# evalboard-005.net
KiCad netlist of a schematic drawn in EAGLE
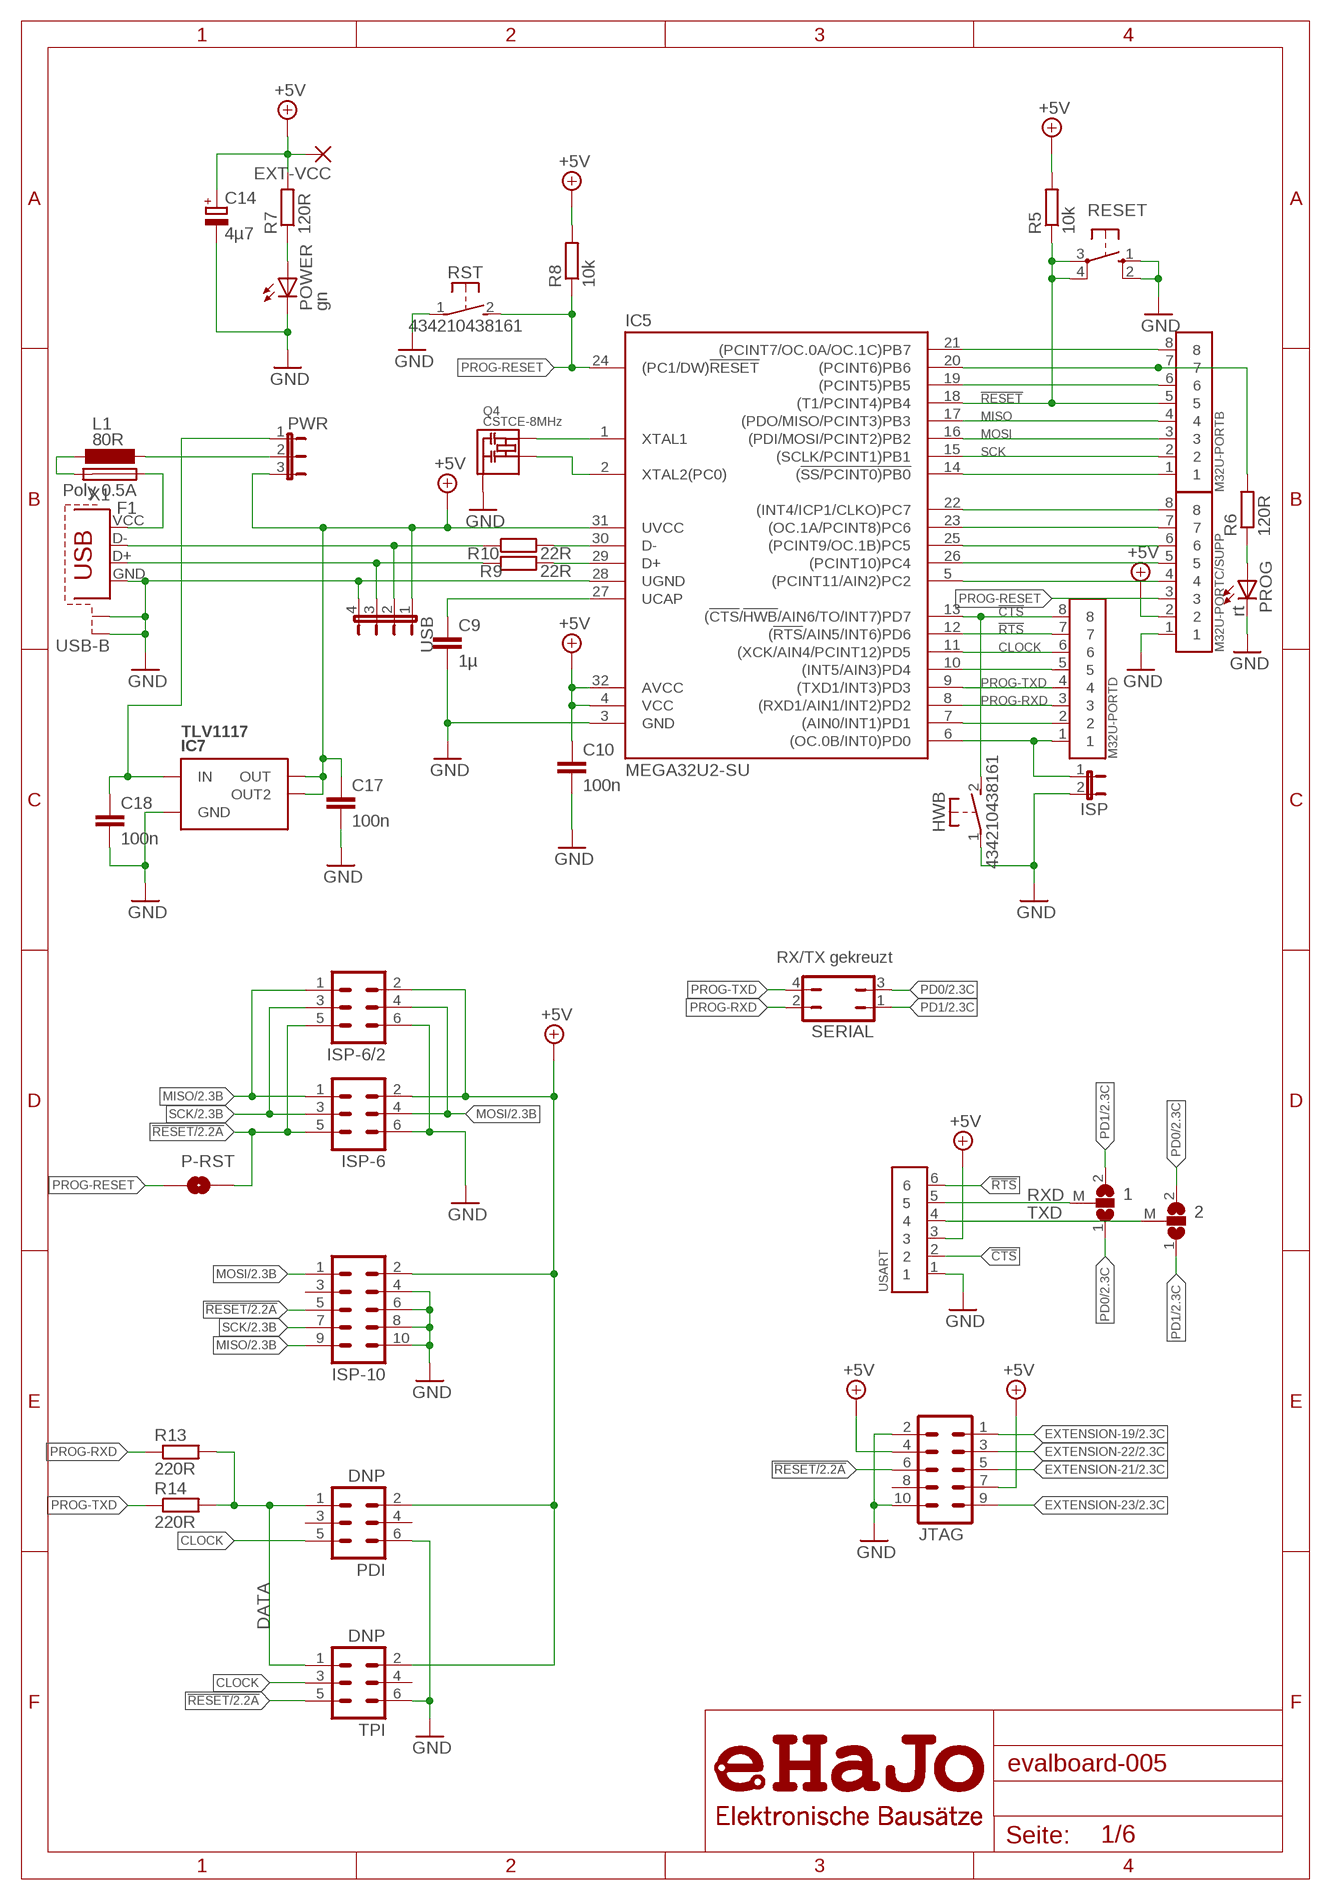
[diagram p0: schematic, sheet 1]
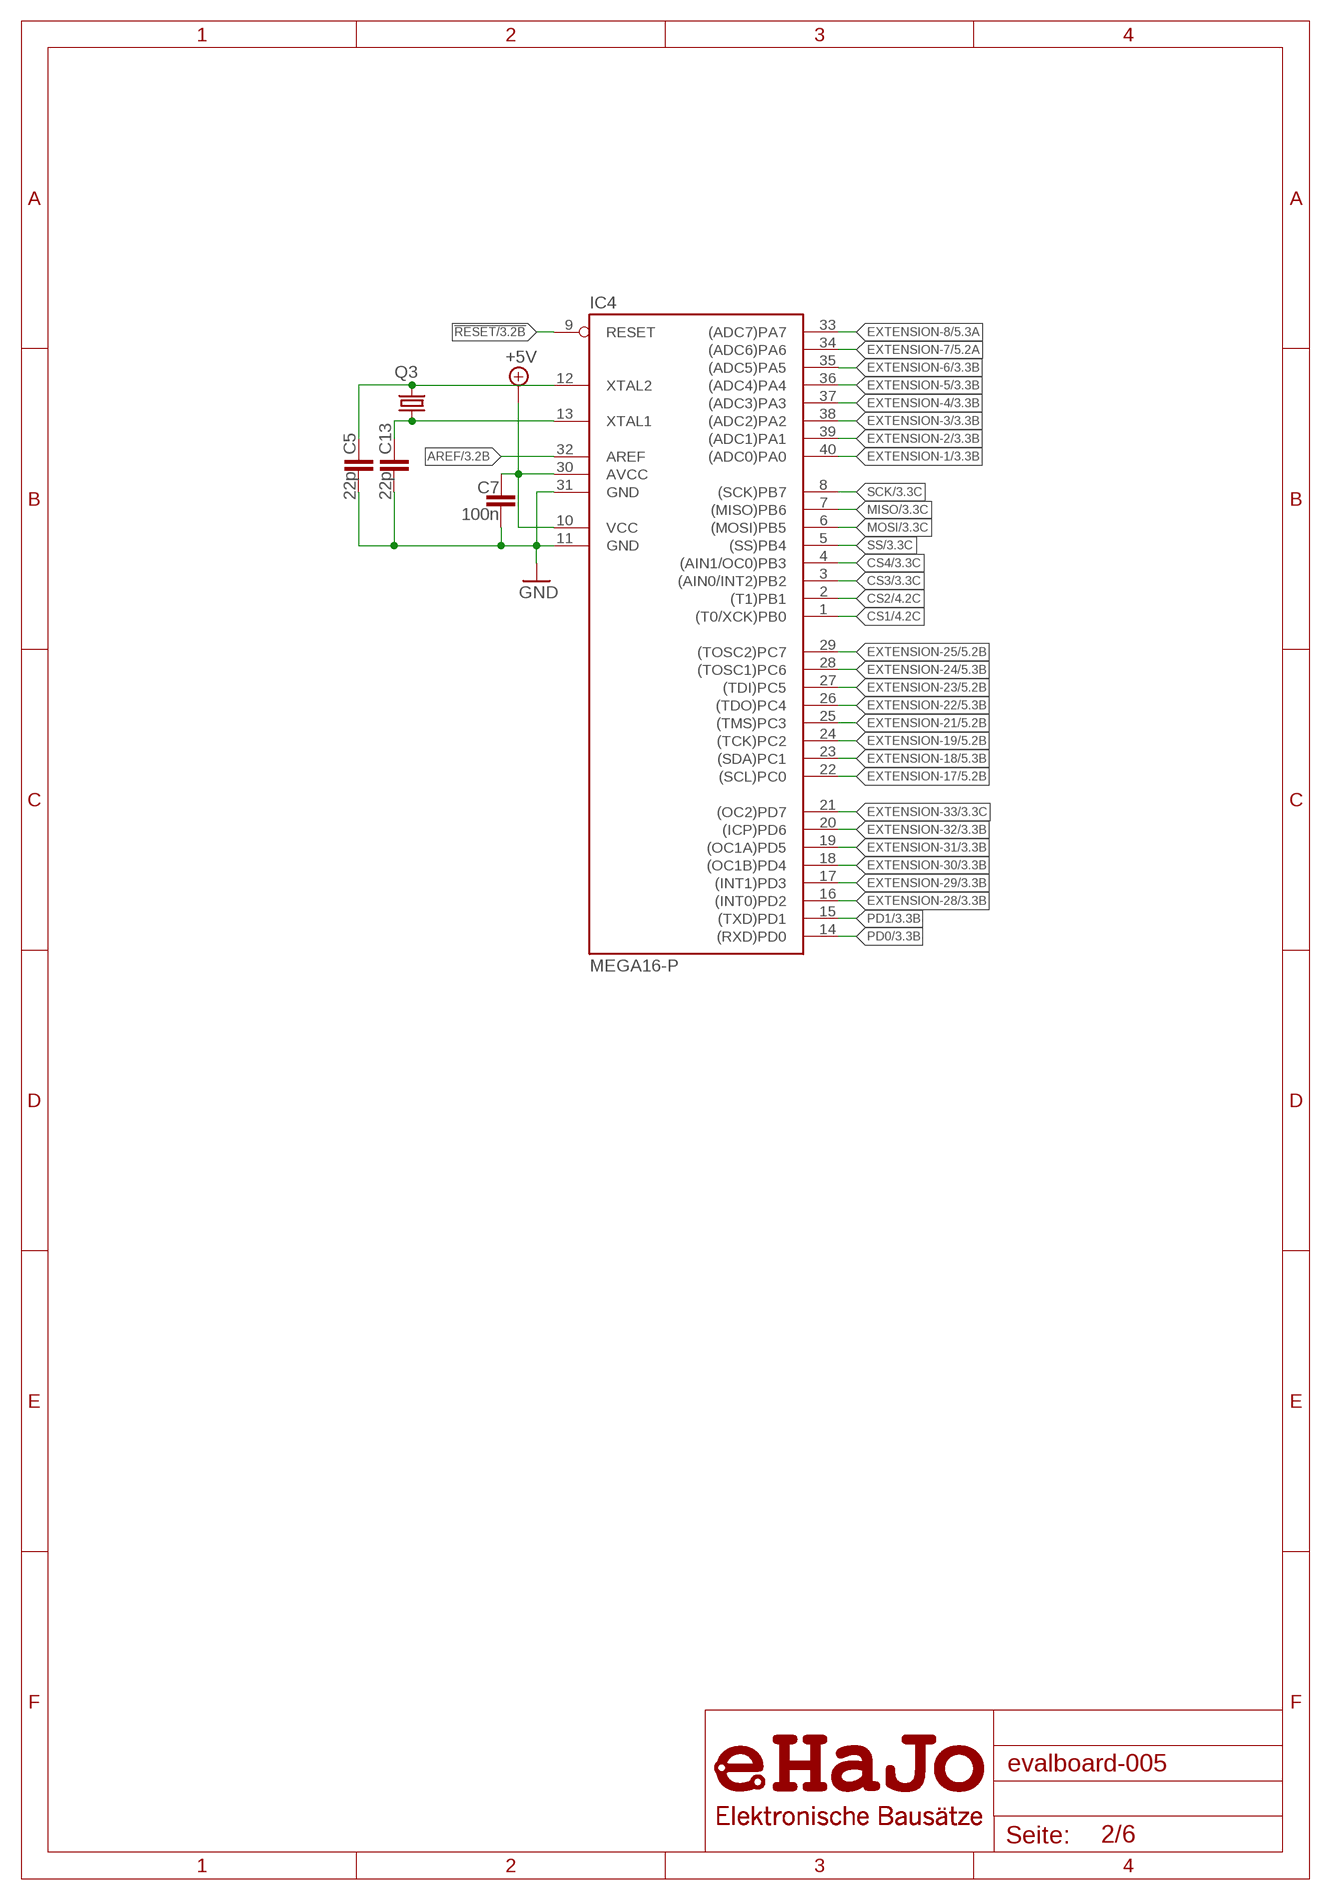
[diagram p1: schematic, sheet 2]
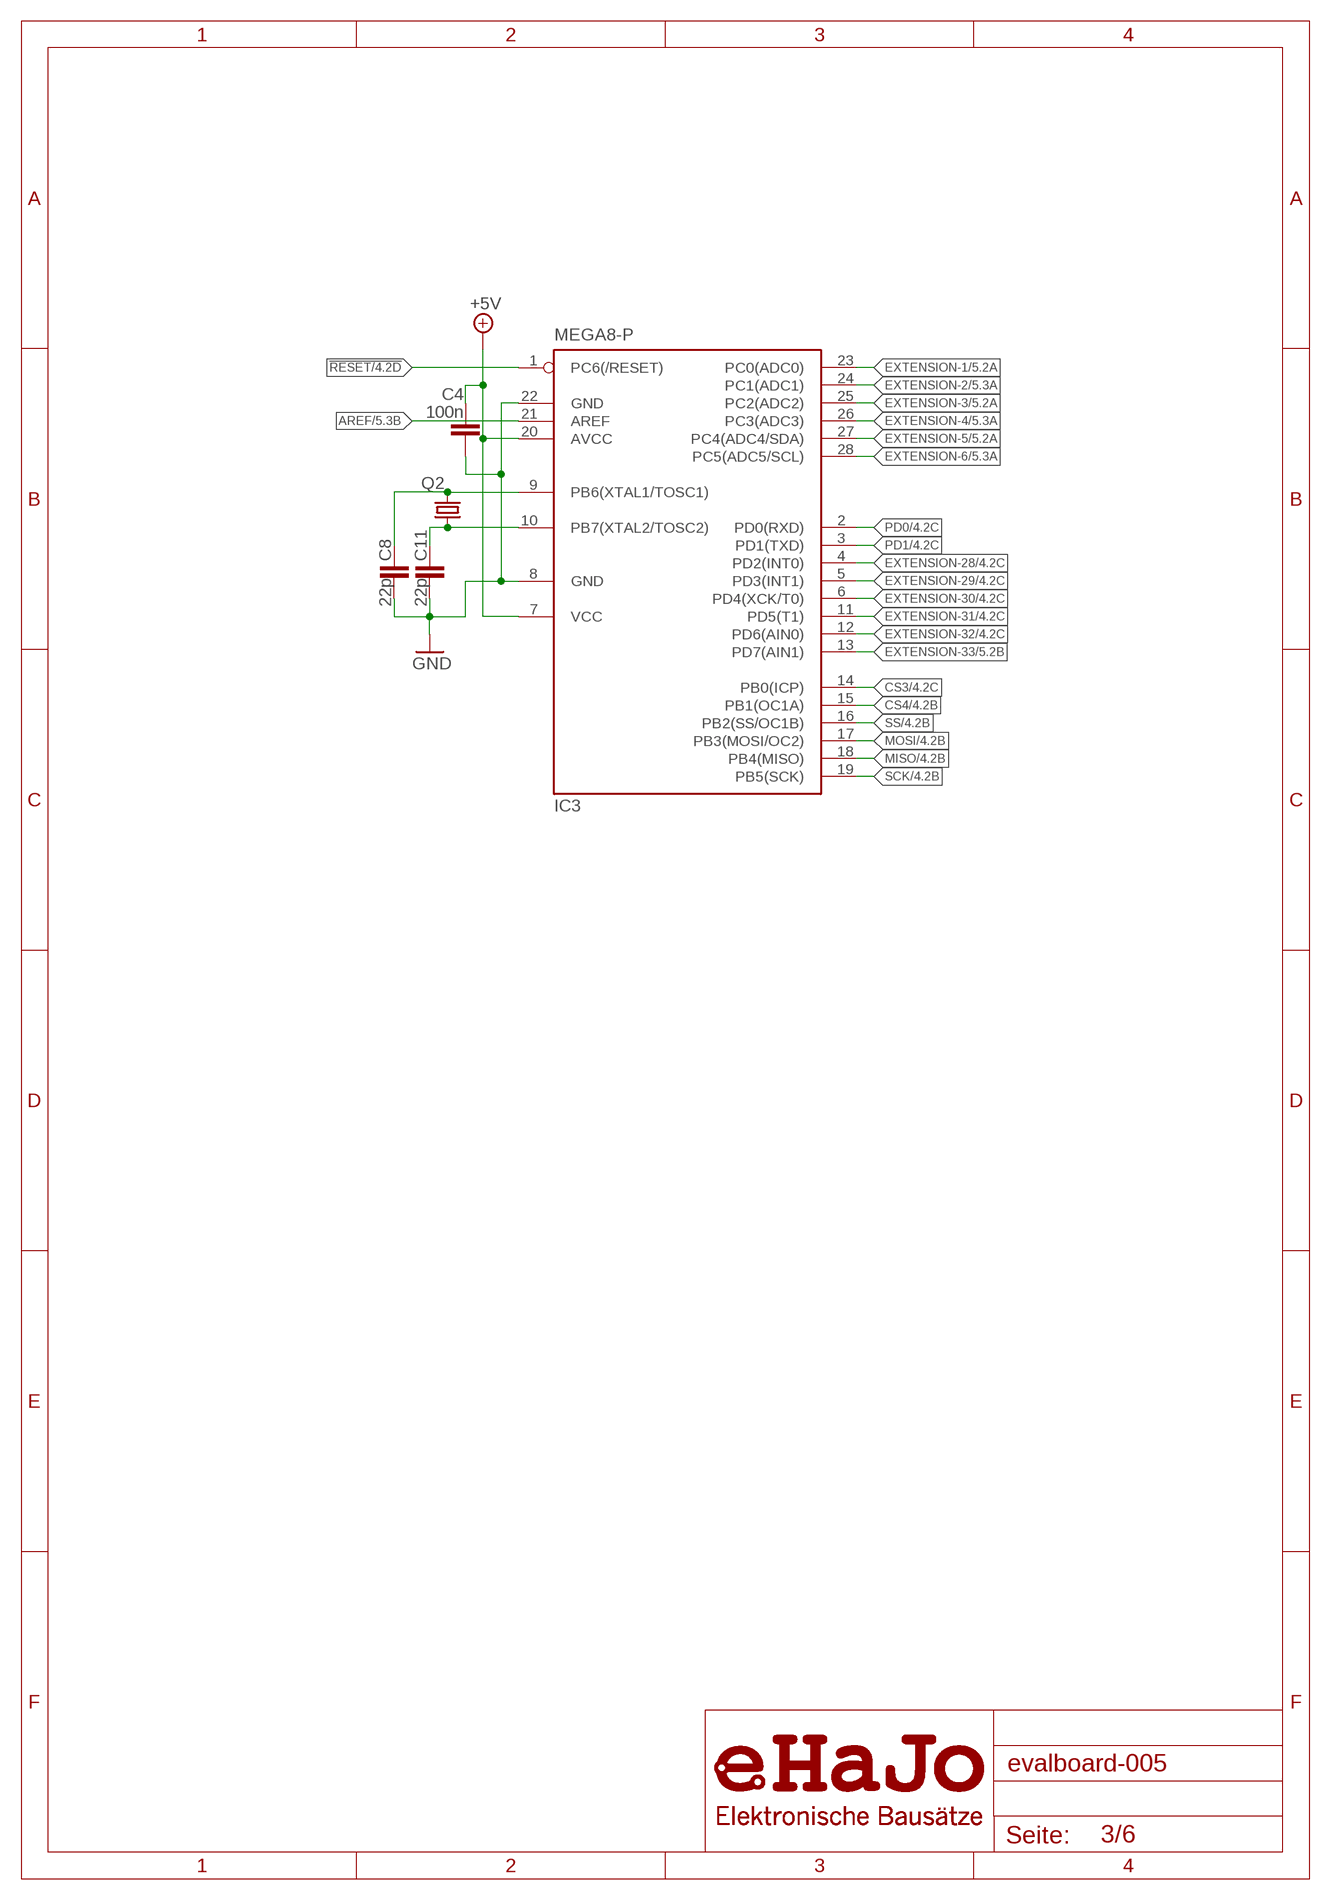
[diagram p2: schematic, sheet 3]
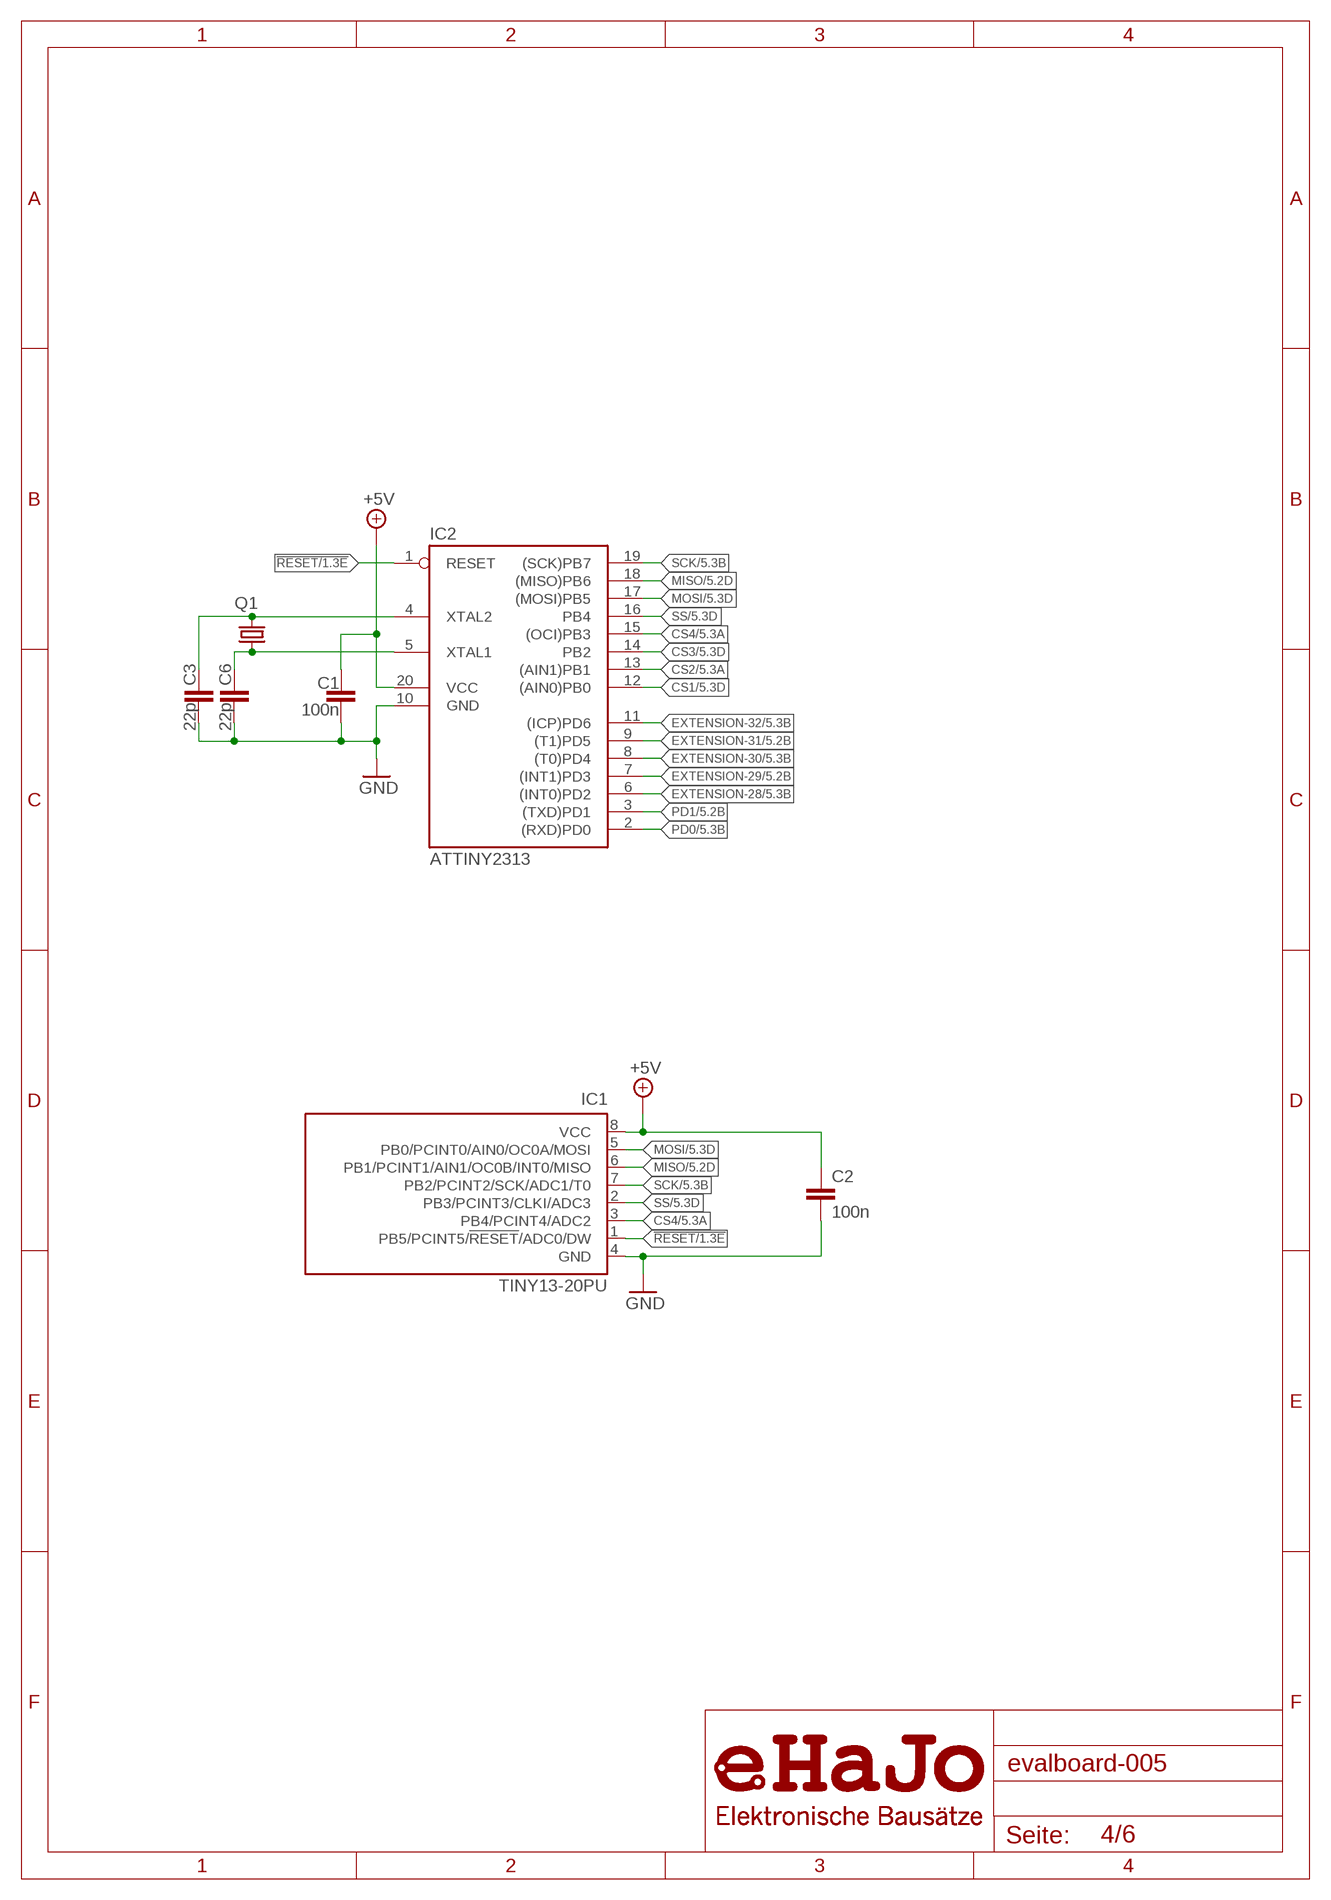
[diagram p3: schematic, sheet 4]
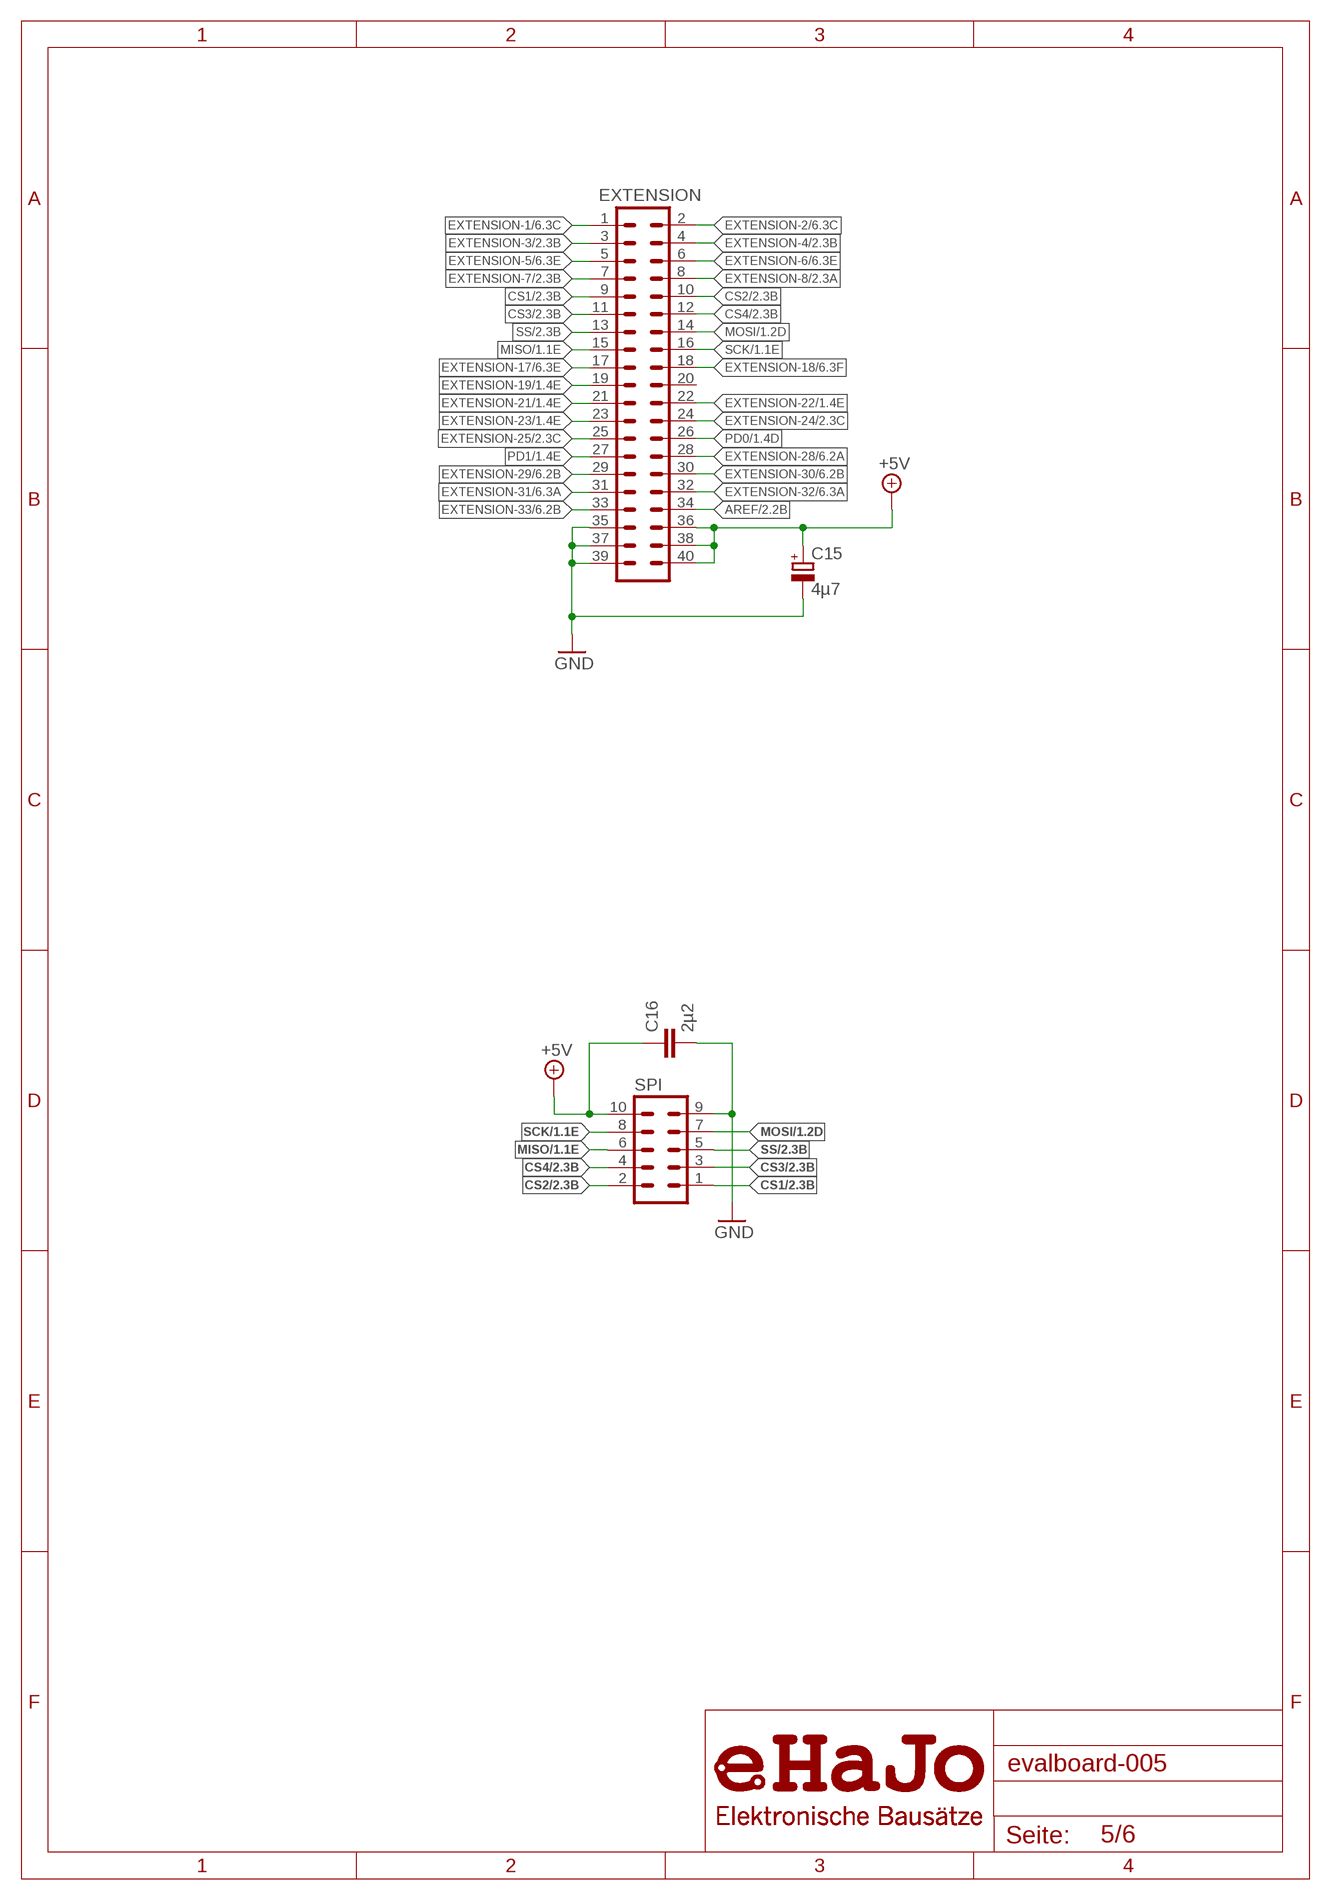
[diagram p4: schematic, sheet 5]
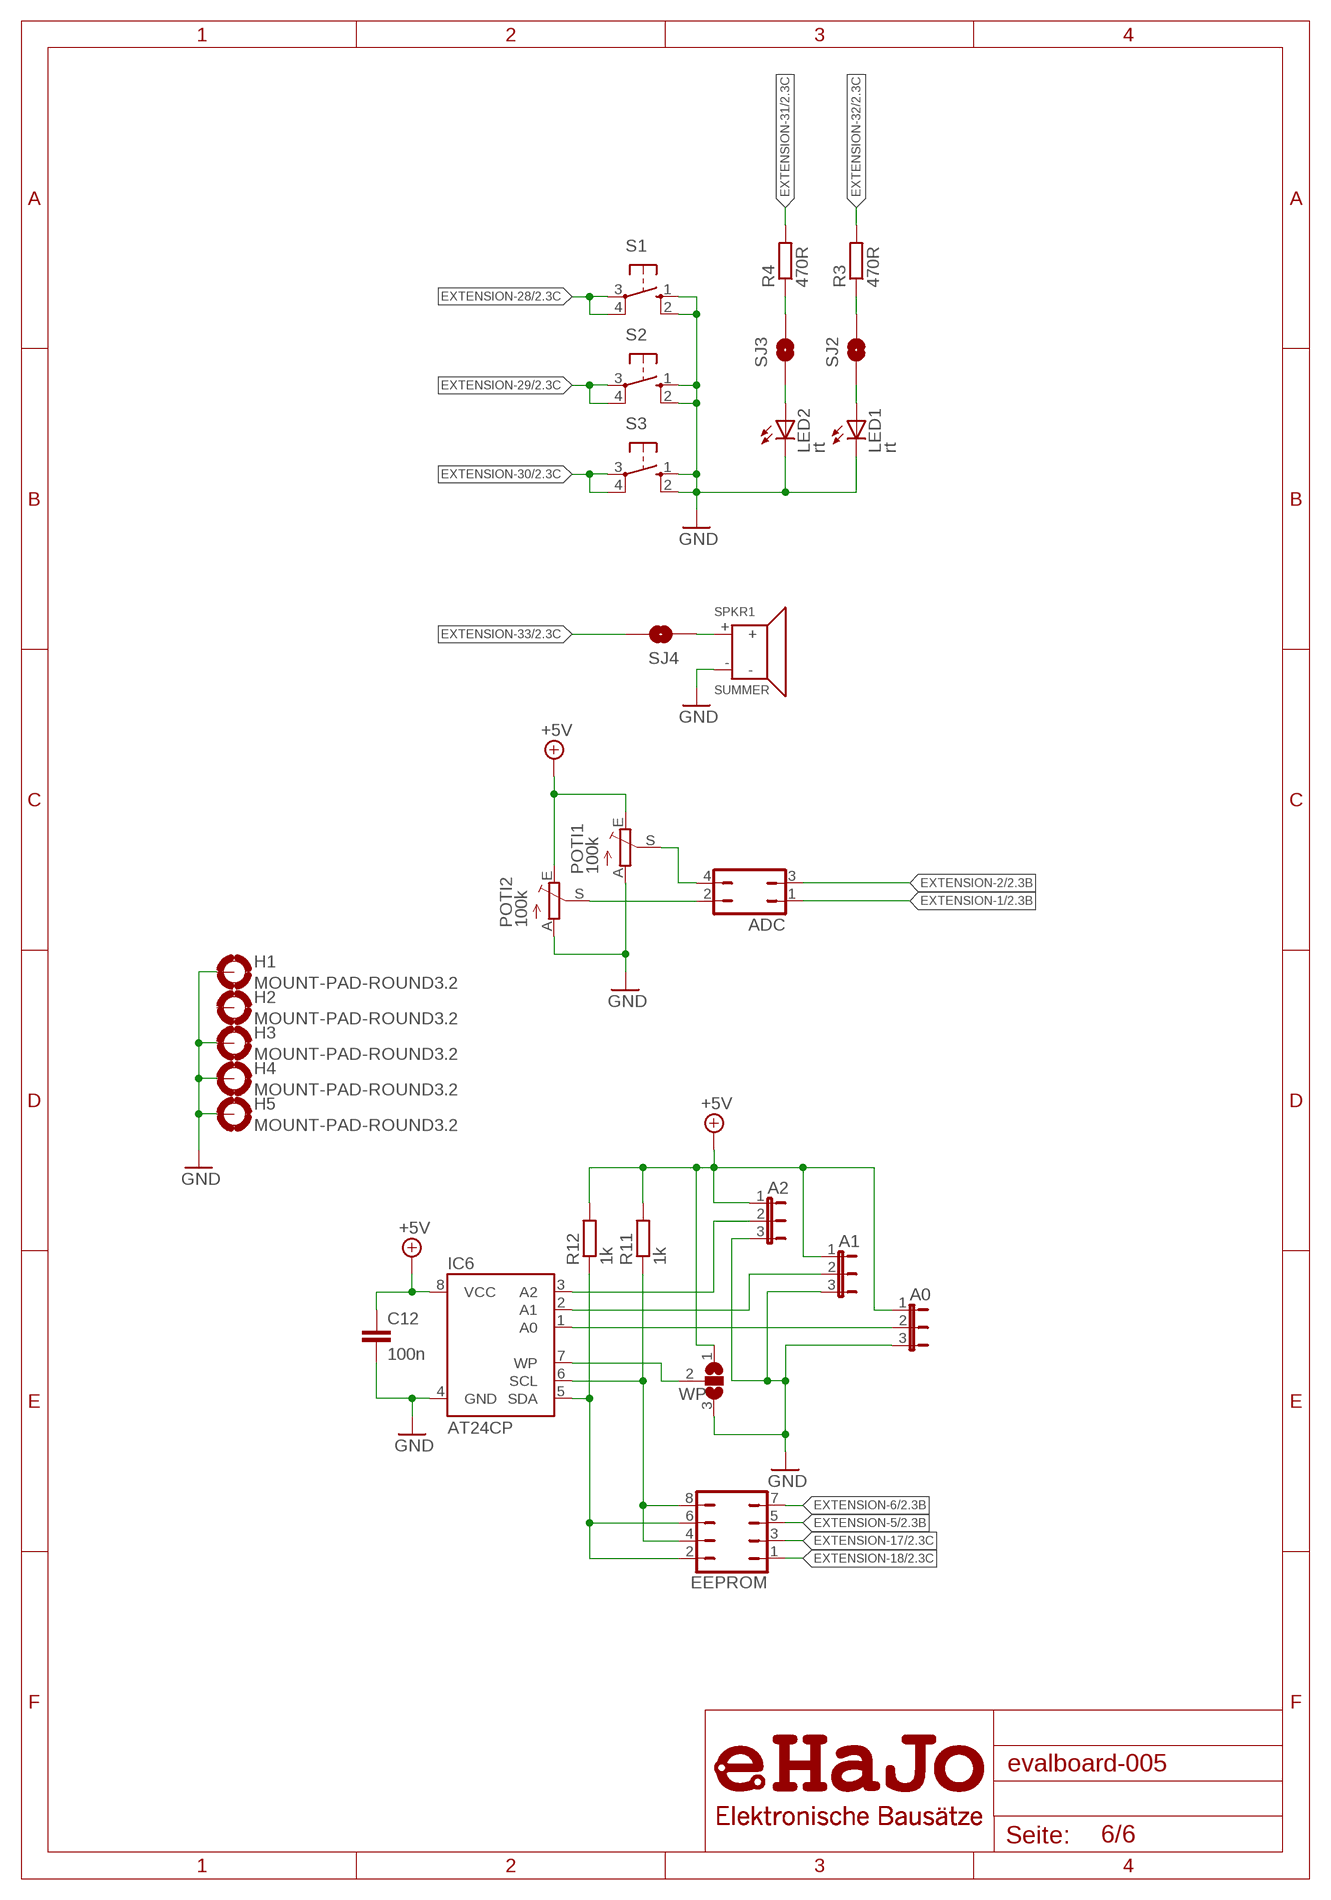
[diagram p5: schematic, sheet 6]

(export (version "E")
  (design (tool "Eeschema 10.0.6"))
  (components
    (comp (ref "1")
      (value "SJ2WS")
      (footprint "eagle-import:SJ2-S")
      (libsource (lib "eagle-import") (part "SJ2WS"))
    )
    (comp (ref "2")
      (value "SJ2WS")
      (footprint "eagle-import:SJ2-S")
      (libsource (lib "eagle-import") (part "SJ2WS"))
    )
    (comp (ref "C9")
      (value "1µ")
      (footprint "eagle-import:C0805")
      (libsource (lib "eagle-import") (part "CC0805"))
    )
    (comp (ref "C10")
      (value "100n")
      (footprint "eagle-import:C0805")
      (libsource (lib "eagle-import") (part "CC0805"))
    )
    (comp (ref "C14")
      (value "4µ7")
      (footprint "eagle-import:E2,5-6E")
      (libsource (lib "eagle-import") (part "CPOLE2,5-6E"))
    )
    (comp (ref "C17")
      (value "100n")
      (footprint "eagle-import:C0805")
      (libsource (lib "eagle-import") (part "CC0805"))
    )
    (comp (ref "C18")
      (value "100n")
      (footprint "eagle-import:C0805")
      (libsource (lib "eagle-import") (part "CC0805"))
    )
    (comp (ref "EXT-VCC")
      (value "2,54/1,0")
      (footprint "eagle-import:2,54_1,0")
      (libsource (lib "eagle-import") (part "2,54/1,0"))
    )
    (comp (ref "F1")
      (value "Poly 0.5A")
      (footprint "eagle-import:1206")
      (libsource (lib "eagle-import") (part "FUSE1206"))
    )
    (comp (ref "HWB")
      (value "434210438161")
      (footprint "eagle-import:WS-TRS-6,0X3,5")
      (libsource (lib "eagle-import") (part "434121043816"))
    )
    (comp (ref "IC5")
      (value "MEGA32U2-SU")
      (footprint "eagle-import:TQFP32-08")
      (libsource (lib "eagle-import") (part "MEGA8U-SU"))
    )
    (comp (ref "IC7")
      (value "TLV1117")
      (footprint "eagle-import:SOT-223-4")
      (libsource (lib "eagle-import") (part "TLV1117"))
    )
    (comp (ref "ISP")
      (value "JP1E")
      (footprint "eagle-import:JP1")
      (libsource (lib "eagle-import") (part "JP1E"))
    )
    (comp (ref "ISP-6")
      (value "ML6")
      (footprint "eagle-import:ML6")
      (libsource (lib "eagle-import") (part "ML6"))
    )
    (comp (ref "ISP-6/2")
      (value "ML6")
      (footprint "eagle-import:ML6")
      (libsource (lib "eagle-import") (part "ML6"))
    )
    (comp (ref "ISP-10")
      (value "ML10")
      (footprint "eagle-import:ML10")
      (libsource (lib "eagle-import") (part "ML10"))
    )
    (comp (ref "JTAG")
      (value "ML10")
      (footprint "eagle-import:ML10")
      (libsource (lib "eagle-import") (part "ML10"))
    )
    (comp (ref "L1")
      (value "80R")
      (footprint "eagle-import:L2012C")
      (libsource (lib "eagle-import") (part "LL2012C"))
    )
    (comp (ref "M32U-PORTB")
      (value "JP8E")
      (footprint "eagle-import:JP8E")
      (libsource (lib "eagle-import") (part "JP8E"))
    )
    (comp (ref "M32U-PORTC/SUPP")
      (value "JP8E")
      (footprint "eagle-import:JP8E")
      (libsource (lib "eagle-import") (part "JP8E"))
    )
    (comp (ref "M32U-PORTD")
      (value "JP8E")
      (footprint "eagle-import:JP8E")
      (libsource (lib "eagle-import") (part "JP8E"))
    )
    (comp (ref "P-RST")
      (value "SJS")
      (footprint "eagle-import:SJS")
      (libsource (lib "eagle-import") (part "SJS"))
    )
    (comp (ref "PDI")
      (value "DNP")
      (footprint "eagle-import:ML6")
      (libsource (lib "eagle-import") (part "ML6"))
    )
    (comp (ref "POWER")
      (value "gn")
      (footprint "eagle-import:CHIP-LED0805")
      (libsource (lib "eagle-import") (part "LEDCHIP-LED0805"))
    )
    (comp (ref "PROG")
      (value "rt")
      (footprint "eagle-import:CHIP-LED0805")
      (libsource (lib "eagle-import") (part "LEDCHIP-LED0805"))
    )
    (comp (ref "PWR")
      (value "JP2E")
      (footprint "eagle-import:JP2")
      (libsource (lib "eagle-import") (part "JP2E"))
    )
    (comp (ref "Q4")
      (value "CSTCE-8MHz")
      (footprint "eagle-import:SMALL-CAP")
      (libsource (lib "eagle-import") (part "CSTCE"))
    )
    (comp (ref "R5")
      (value "10k")
      (footprint "eagle-import:R0805")
      (libsource (lib "eagle-import") (part "RR0805"))
    )
    (comp (ref "R6")
      (value "120R")
      (footprint "eagle-import:R0805")
      (libsource (lib "eagle-import") (part "RR0805"))
    )
    (comp (ref "R7")
      (value "120R")
      (footprint "eagle-import:R0805")
      (libsource (lib "eagle-import") (part "RR0805"))
    )
    (comp (ref "R8")
      (value "10k")
      (footprint "eagle-import:R0805")
      (libsource (lib "eagle-import") (part "RR0805"))
    )
    (comp (ref "R9")
      (value "22R")
      (footprint "eagle-import:R0805")
      (libsource (lib "eagle-import") (part "RR0805"))
    )
    (comp (ref "R10")
      (value "22R")
      (footprint "eagle-import:R0805")
      (libsource (lib "eagle-import") (part "RR0805"))
    )
    (comp (ref "R13")
      (value "220R")
      (footprint "eagle-import:R0805")
      (libsource (lib "eagle-import") (part "RR0805"))
    )
    (comp (ref "R14")
      (value "220R")
      (footprint "eagle-import:R0805")
      (libsource (lib "eagle-import") (part "RR0805"))
    )
    (comp (ref "RESET")
      (value "10-XX")
      (footprint "eagle-import:B3F-10XX")
      (libsource (lib "eagle-import") (part "10-XX"))
    )
    (comp (ref "RST")
      (value "434210438161")
      (footprint "eagle-import:WS-TRS-6,0X3,5")
      (libsource (lib "eagle-import") (part "434121043816"))
    )
    (comp (ref "SERIAL")
      (value "JP2Q")
      (footprint "eagle-import:JP2Q")
      (libsource (lib "eagle-import") (part "JP2Q"))
    )
    (comp (ref "TPI")
      (value "DNP")
      (footprint "eagle-import:ML6")
      (libsource (lib "eagle-import") (part "ML6"))
    )
    (comp (ref "USART")
      (value "JP6E")
      (footprint "eagle-import:JP6E")
      (libsource (lib "eagle-import") (part "JP6E"))
    )
    (comp (ref "USB")
      (value "JP4E")
      (footprint "eagle-import:JP4")
      (libsource (lib "eagle-import") (part "JP4E"))
    )
    (comp (ref "X1")
      (value "USB-B")
      (footprint "eagle-import:PN61729-S")
      (libsource (lib "eagle-import") (part "USB-B"))
    )
    (comp (ref "C4")
      (value "100n")
      (footprint "eagle-import:C0805")
      (libsource (lib "eagle-import") (part "CC0805"))
    )
    (comp (ref "C8")
      (value "22p")
      (footprint "eagle-import:C0805")
      (libsource (lib "eagle-import") (part "CC0805"))
    )
    (comp (ref "C11")
      (value "22p")
      (footprint "eagle-import:C0805")
      (libsource (lib "eagle-import") (part "CC0805"))
    )
    (comp (ref "IC3")
      (value "MEGA8-P")
      (footprint "eagle-import:DIL28-3")
      (libsource (lib "eagle-import") (part "MEGA8-P"))
    )
    (comp (ref "Q2")
      (value "CRYSTALHC49U70")
      (footprint "eagle-import:HC49U70")
      (libsource (lib "eagle-import") (part "CRYSTALHC49U70"))
    )
    (comp (ref "C5")
      (value "22p")
      (footprint "eagle-import:C0805")
      (libsource (lib "eagle-import") (part "CC0805"))
    )
    (comp (ref "C7")
      (value "100n")
      (footprint "eagle-import:C0805")
      (libsource (lib "eagle-import") (part "CC0805"))
    )
    (comp (ref "C13")
      (value "22p")
      (footprint "eagle-import:C0805")
      (libsource (lib "eagle-import") (part "CC0805"))
    )
    (comp (ref "IC4")
      (value "MEGA16-P")
      (footprint "eagle-import:DIL40")
      (libsource (lib "eagle-import") (part "MEGA16-P"))
    )
    (comp (ref "Q3")
      (value "CRYSTALHC49U70")
      (footprint "eagle-import:HC49U70")
      (libsource (lib "eagle-import") (part "CRYSTALHC49U70"))
    )
    (comp (ref "A0")
      (value "JP2E")
      (footprint "eagle-import:JP2")
      (libsource (lib "eagle-import") (part "JP2E"))
    )
    (comp (ref "A1")
      (value "JP2E")
      (footprint "eagle-import:JP2")
      (libsource (lib "eagle-import") (part "JP2E"))
    )
    (comp (ref "A2")
      (value "JP2E")
      (footprint "eagle-import:JP2")
      (libsource (lib "eagle-import") (part "JP2E"))
    )
    (comp (ref "ADC")
      (value "JP2Q")
      (footprint "eagle-import:JP2Q")
      (libsource (lib "eagle-import") (part "JP2Q"))
    )
    (comp (ref "C12")
      (value "100n")
      (footprint "eagle-import:C0805")
      (libsource (lib "eagle-import") (part "CC0805"))
    )
    (comp (ref "EEPROM")
      (value "JP4Q")
      (footprint "eagle-import:JP4Q")
      (libsource (lib "eagle-import") (part "JP4Q"))
    )
    (comp (ref "H1")
      (value "MOUNT-PAD-ROUND3.2")
      (footprint "eagle-import:3,2-PAD")
      (libsource (lib "eagle-import") (part "MOUNT-PAD-ROUND3.2"))
    )
    (comp (ref "H2")
      (value "MOUNT-PAD-ROUND3.2")
      (footprint "eagle-import:3,2-PAD")
      (libsource (lib "eagle-import") (part "MOUNT-PAD-ROUND3.2"))
    )
    (comp (ref "H3")
      (value "MOUNT-PAD-ROUND3.2")
      (footprint "eagle-import:3,2-PAD")
      (libsource (lib "eagle-import") (part "MOUNT-PAD-ROUND3.2"))
    )
    (comp (ref "H4")
      (value "MOUNT-PAD-ROUND3.2")
      (footprint "eagle-import:3,2-PAD")
      (libsource (lib "eagle-import") (part "MOUNT-PAD-ROUND3.2"))
    )
    (comp (ref "H5")
      (value "MOUNT-PAD-ROUND3.2")
      (footprint "eagle-import:3,2-PAD")
      (libsource (lib "eagle-import") (part "MOUNT-PAD-ROUND3.2"))
    )
    (comp (ref "IC6")
      (value "AT24CP")
      (footprint "eagle-import:DIL08")
      (libsource (lib "eagle-import") (part "AT24CP"))
    )
    (comp (ref "LED1")
      (value "rt")
      (footprint "eagle-import:LED5MM")
      (libsource (lib "eagle-import") (part "LED5MM"))
    )
    (comp (ref "LED2")
      (value "rt")
      (footprint "eagle-import:LED5MM")
      (libsource (lib "eagle-import") (part "LED5MM"))
    )
    (comp (ref "POTI1")
      (value "100k")
      (footprint "eagle-import:PT-6")
      (libsource (lib "eagle-import") (part "POTIPT6"))
    )
    (comp (ref "POTI2")
      (value "100k")
      (footprint "eagle-import:PT-6")
      (libsource (lib "eagle-import") (part "POTIPT6"))
    )
    (comp (ref "R3")
      (value "470R")
      (footprint "eagle-import:R0805")
      (libsource (lib "eagle-import") (part "RR0805"))
    )
    (comp (ref "R4")
      (value "470R")
      (footprint "eagle-import:R0805")
      (libsource (lib "eagle-import") (part "RR0805"))
    )
    (comp (ref "R11")
      (value "1k")
      (footprint "eagle-import:R0805")
      (libsource (lib "eagle-import") (part "RR0805"))
    )
    (comp (ref "R12")
      (value "1k")
      (footprint "eagle-import:R0805")
      (libsource (lib "eagle-import") (part "RR0805"))
    )
    (comp (ref "S1")
      (value "10-XX")
      (footprint "eagle-import:B3F-10XX")
      (libsource (lib "eagle-import") (part "10-XX"))
    )
    (comp (ref "S2")
      (value "10-XX")
      (footprint "eagle-import:B3F-10XX")
      (libsource (lib "eagle-import") (part "10-XX"))
    )
    (comp (ref "S3")
      (value "10-XX")
      (footprint "eagle-import:B3F-10XX")
      (libsource (lib "eagle-import") (part "10-XX"))
    )
    (comp (ref "SJ2")
      (value "SJS")
      (footprint "eagle-import:SJS")
      (libsource (lib "eagle-import") (part "SJS"))
    )
    (comp (ref "SJ3")
      (value "SJS")
      (footprint "eagle-import:SJS")
      (libsource (lib "eagle-import") (part "SJS"))
    )
    (comp (ref "SJ4")
      (value "SJS")
      (footprint "eagle-import:SJS")
      (libsource (lib "eagle-import") (part "SJS"))
    )
    (comp (ref "SPKR1")
      (value "SUMMER")
      (footprint "eagle-import:SUMMER")
      (libsource (lib "eagle-import") (part "SUMMER"))
    )
    (comp (ref "WP")
      (value "SJ2W")
      (footprint "eagle-import:SJ_2")
      (libsource (lib "eagle-import") (part "SJ2W"))
    )
    (comp (ref "C15")
      (value "4µ7")
      (footprint "eagle-import:E2,5-6E")
      (libsource (lib "eagle-import") (part "CPOLE2,5-6E"))
    )
    (comp (ref "C16")
      (value "2µ2")
      (footprint "eagle-import:C0805")
      (libsource (lib "eagle-import") (part "CC0805"))
    )
    (comp (ref "EXTENSION")
      (value "ML40")
      (footprint "eagle-import:ML40")
      (libsource (lib "eagle-import") (part "ML40"))
    )
    (comp (ref "SPI")
      (value "ML10")
      (footprint "eagle-import:ML10")
      (libsource (lib "eagle-import") (part "ML10"))
    )
    (comp (ref "C1")
      (value "100n")
      (footprint "eagle-import:C0805")
      (libsource (lib "eagle-import") (part "CC0805"))
    )
    (comp (ref "C2")
      (value "100n")
      (footprint "eagle-import:C0805")
      (libsource (lib "eagle-import") (part "CC0805"))
    )
    (comp (ref "C3")
      (value "22p")
      (footprint "eagle-import:C0805")
      (libsource (lib "eagle-import") (part "CC0805"))
    )
    (comp (ref "C6")
      (value "22p")
      (footprint "eagle-import:C0805")
      (libsource (lib "eagle-import") (part "CC0805"))
    )
    (comp (ref "IC1")
      (value "TINY13-20PU")
      (footprint "eagle-import:DIL08")
      (libsource (lib "eagle-import") (part "TINY13PU-20"))
    )
    (comp (ref "IC2")
      (value "ATTINY2313")
      (footprint "eagle-import:DIL20")
      (libsource (lib "eagle-import") (part "AT90S2313P"))
    )
    (comp (ref "Q1")
      (value "CRYSTALHC49U70")
      (footprint "eagle-import:HC49U70")
      (libsource (lib "eagle-import") (part "CRYSTALHC49U70"))
    )
  )
  (nets
    (net (code "1") (name "+5V") (class "Default")
      (node (ref "A0") (pin "1") (pinfunction "1_1") (pintype "passive"))
      (node (ref "A1") (pin "1") (pinfunction "1_1") (pintype "passive"))
      (node (ref "A2") (pin "1") (pinfunction "1_1") (pintype "passive"))
      (node (ref "C1") (pin "1") (pinfunction "1_1") (pintype "passive"))
      (node (ref "C10") (pin "1") (pinfunction "1_1") (pintype "passive"))
      (node (ref "C12") (pin "1") (pinfunction "1_1") (pintype "passive"))
      (node (ref "C14") (pin "+") (pinfunction "+_+") (pintype "passive"))
      (node (ref "C15") (pin "+") (pinfunction "+_+") (pintype "passive"))
      (node (ref "C16") (pin "1") (pinfunction "1_1") (pintype "passive"))
      (node (ref "C17") (pin "1") (pinfunction "1_1") (pintype "passive"))
      (node (ref "C2") (pin "1") (pinfunction "1_1") (pintype "passive"))
      (node (ref "C4") (pin "1") (pinfunction "1_1") (pintype "passive"))
      (node (ref "C7") (pin "1") (pinfunction "1_1") (pintype "passive"))
      (node (ref "EXT-VCC") (pin "1") (pinfunction "P_1") (pintype "passive"))
      (node (ref "EXTENSION") (pin "36") (pinfunction "36_36") (pintype "passive"))
      (node (ref "EXTENSION") (pin "38") (pinfunction "38_38") (pintype "passive"))
      (node (ref "EXTENSION") (pin "40") (pinfunction "40_40") (pintype "passive"))
      (node (ref "IC1") (pin "8") (pinfunction "VCC_8") (pintype "power_in"))
      (node (ref "IC2") (pin "20") (pinfunction "VCC_20") (pintype "power_in"))
      (node (ref "IC3") (pin "20") (pinfunction "AVCC_20") (pintype "power_in"))
      (node (ref "IC3") (pin "7") (pinfunction "VCC_7") (pintype "power_in"))
      (node (ref "IC4") (pin "10") (pinfunction "VCC_10") (pintype "power_in"))
      (node (ref "IC4") (pin "30") (pinfunction "AVCC_30") (pintype "power_in"))
      (node (ref "IC5") (pin "31") (pinfunction "UVCC_31") (pintype "power_in"))
      (node (ref "IC5") (pin "32") (pinfunction "AVCC_32") (pintype "power_in"))
      (node (ref "IC5") (pin "4") (pinfunction "VCC_4") (pintype "power_in"))
      (node (ref "IC6") (pin "8") (pinfunction "VCC_8") (pintype "power_in"))
      (node (ref "IC7") (pin "2") (pinfunction "OUT_2") (pintype "bidirectional"))
      (node (ref "IC7") (pin "4") (pinfunction "OUT2_4") (pintype "bidirectional"))
      (node (ref "ISP-10") (pin "2") (pinfunction "2_2") (pintype "passive"))
      (node (ref "ISP-6") (pin "2") (pinfunction "2_2") (pintype "passive"))
      (node (ref "ISP-6/2") (pin "2") (pinfunction "2_2") (pintype "passive"))
      (node (ref "JTAG") (pin "4") (pinfunction "4_4") (pintype "passive"))
      (node (ref "JTAG") (pin "7") (pinfunction "7_7") (pintype "passive"))
      (node (ref "M32U-PORTC/SUPP") (pin "2") (pinfunction "2_2") (pintype "bidirectional"))
      (node (ref "PDI") (pin "2") (pinfunction "2_2") (pintype "passive"))
      (node (ref "POTI1") (pin "E") (pinfunction "E_E") (pintype "passive"))
      (node (ref "POTI2") (pin "E") (pinfunction "E_E") (pintype "passive"))
      (node (ref "PWR") (pin "3") (pinfunction "3_3") (pintype "passive"))
      (node (ref "R11") (pin "2") (pinfunction "2_2") (pintype "passive"))
      (node (ref "R12") (pin "2") (pinfunction "2_2") (pintype "passive"))
      (node (ref "R5") (pin "2") (pinfunction "2_2") (pintype "passive"))
      (node (ref "R7") (pin "2") (pinfunction "2_2") (pintype "passive"))
      (node (ref "R8") (pin "2") (pinfunction "2_2") (pintype "passive"))
      (node (ref "SPI") (pin "10") (pinfunction "10_10") (pintype "passive"))
      (node (ref "TPI") (pin "2") (pinfunction "2_2") (pintype "passive"))
      (node (ref "USART") (pin "3") (pinfunction "3_3") (pintype "bidirectional"))
      (node (ref "USB") (pin "1") (pinfunction "1_1") (pintype "passive"))
      (node (ref "WP") (pin "1") (pinfunction "1_1") (pintype "passive"))
    )
    (net (code "2") (name "AREF") (class "Default")
      (node (ref "EXTENSION") (pin "34") (pinfunction "34_34") (pintype "passive"))
      (node (ref "IC3") (pin "21") (pinfunction "AREF_21") (pintype "passive"))
      (node (ref "IC4") (pin "32") (pinfunction "AREF_32") (pintype "passive"))
    )
    (net (code "3") (name "CLOCK") (class "Default")
      (node (ref "IC5") (pin "11") (pinfunction "(XCK/AIN4/PCINT12)PD5_11") (pintype "bidirectional"))
      (node (ref "M32U-PORTD") (pin "6") (pinfunction "6_6") (pintype "bidirectional"))
      (node (ref "PDI") (pin "5") (pinfunction "5_5") (pintype "passive"))
      (node (ref "TPI") (pin "3") (pinfunction "3_3") (pintype "passive"))
    )
    (net (code "4") (name "CS1") (class "Default")
      (node (ref "EXTENSION") (pin "9") (pinfunction "9_9") (pintype "passive"))
      (node (ref "IC2") (pin "12") (pinfunction "(AIN0)PB0_12") (pintype "bidirectional"))
      (node (ref "IC4") (pin "1") (pinfunction "(T0/XCK)PB0_1") (pintype "bidirectional"))
      (node (ref "SPI") (pin "1") (pinfunction "1_1") (pintype "passive"))
    )
    (net (code "5") (name "CS2") (class "Default")
      (node (ref "EXTENSION") (pin "10") (pinfunction "10_10") (pintype "passive"))
      (node (ref "IC2") (pin "13") (pinfunction "(AIN1)PB1_13") (pintype "bidirectional"))
      (node (ref "IC4") (pin "2") (pinfunction "(T1)PB1_2") (pintype "bidirectional"))
      (node (ref "SPI") (pin "2") (pinfunction "2_2") (pintype "passive"))
    )
    (net (code "6") (name "CS3") (class "Default")
      (node (ref "EXTENSION") (pin "11") (pinfunction "11_11") (pintype "passive"))
      (node (ref "IC2") (pin "14") (pinfunction "PB2_14") (pintype "bidirectional"))
      (node (ref "IC3") (pin "14") (pinfunction "PB0(ICP)_14") (pintype "bidirectional"))
      (node (ref "IC4") (pin "3") (pinfunction "(AIN0/INT2)PB2_3") (pintype "bidirectional"))
      (node (ref "SPI") (pin "3") (pinfunction "3_3") (pintype "passive"))
    )
    (net (code "7") (name "CS4") (class "Default")
      (node (ref "EXTENSION") (pin "12") (pinfunction "12_12") (pintype "passive"))
      (node (ref "IC1") (pin "3") (pinfunction "PB4/PCINT4/ADC2_3") (pintype "bidirectional"))
      (node (ref "IC2") (pin "15") (pinfunction "(OCI)PB3_15") (pintype "bidirectional"))
      (node (ref "IC3") (pin "15") (pinfunction "PB1(OC1A)_15") (pintype "bidirectional"))
      (node (ref "IC4") (pin "4") (pinfunction "(AIN1/OC0)PB3_4") (pintype "bidirectional"))
      (node (ref "SPI") (pin "4") (pinfunction "4_4") (pintype "passive"))
    )
    (net (code "8") (name "DATA") (class "Default")
      (node (ref "PDI") (pin "1") (pinfunction "1_1") (pintype "passive"))
      (node (ref "R13") (pin "2") (pinfunction "2_2") (pintype "passive"))
      (node (ref "R14") (pin "2") (pinfunction "2_2") (pintype "passive"))
      (node (ref "TPI") (pin "1") (pinfunction "1_1") (pintype "passive"))
    )
    (net (code "9") (name "EXTENSION-1") (class "Default")
      (node (ref "ADC") (pin "1") (pinfunction "1_1") (pintype "passive"))
      (node (ref "EXTENSION") (pin "1") (pinfunction "1_1") (pintype "passive"))
      (node (ref "IC3") (pin "23") (pinfunction "PC0(ADC0)_23") (pintype "bidirectional"))
      (node (ref "IC4") (pin "40") (pinfunction "(ADC0)PA0_40") (pintype "bidirectional"))
    )
    (net (code "10") (name "EXTENSION-2") (class "Default")
      (node (ref "ADC") (pin "3") (pinfunction "3_3") (pintype "passive"))
      (node (ref "EXTENSION") (pin "2") (pinfunction "2_2") (pintype "passive"))
      (node (ref "IC3") (pin "24") (pinfunction "PC1(ADC1)_24") (pintype "bidirectional"))
      (node (ref "IC4") (pin "39") (pinfunction "(ADC1)PA1_39") (pintype "bidirectional"))
    )
    (net (code "11") (name "EXTENSION-3") (class "Default")
      (node (ref "EXTENSION") (pin "3") (pinfunction "3_3") (pintype "passive"))
      (node (ref "IC3") (pin "25") (pinfunction "PC2(ADC2)_25") (pintype "bidirectional"))
      (node (ref "IC4") (pin "38") (pinfunction "(ADC2)PA2_38") (pintype "bidirectional"))
    )
    (net (code "12") (name "EXTENSION-4") (class "Default")
      (node (ref "EXTENSION") (pin "4") (pinfunction "4_4") (pintype "passive"))
      (node (ref "IC3") (pin "26") (pinfunction "PC3(ADC3)_26") (pintype "bidirectional"))
      (node (ref "IC4") (pin "37") (pinfunction "(ADC3)PA3_37") (pintype "bidirectional"))
    )
    (net (code "13") (name "EXTENSION-5") (class "Default")
      (node (ref "EEPROM") (pin "5") (pinfunction "5_5") (pintype "passive"))
      (node (ref "EXTENSION") (pin "5") (pinfunction "5_5") (pintype "passive"))
      (node (ref "IC3") (pin "27") (pinfunction "PC4(ADC4/SDA)_27") (pintype "bidirectional"))
      (node (ref "IC4") (pin "36") (pinfunction "(ADC4)PA4_36") (pintype "bidirectional"))
    )
    (net (code "14") (name "EXTENSION-6") (class "Default")
      (node (ref "EEPROM") (pin "7") (pinfunction "7_7") (pintype "passive"))
      (node (ref "EXTENSION") (pin "6") (pinfunction "6_6") (pintype "passive"))
      (node (ref "IC3") (pin "28") (pinfunction "PC5(ADC5/SCL)_28") (pintype "bidirectional"))
      (node (ref "IC4") (pin "35") (pinfunction "(ADC5)PA5_35") (pintype "bidirectional"))
    )
    (net (code "15") (name "EXTENSION-7") (class "Default")
      (node (ref "EXTENSION") (pin "7") (pinfunction "7_7") (pintype "passive"))
      (node (ref "IC4") (pin "34") (pinfunction "(ADC6)PA6_34") (pintype "bidirectional"))
    )
    (net (code "16") (name "EXTENSION-8") (class "Default")
      (node (ref "EXTENSION") (pin "8") (pinfunction "8_8") (pintype "passive"))
      (node (ref "IC4") (pin "33") (pinfunction "(ADC7)PA7_33") (pintype "bidirectional"))
    )
    (net (code "17") (name "EXTENSION-17") (class "Default")
      (node (ref "EEPROM") (pin "3") (pinfunction "3_3") (pintype "passive"))
      (node (ref "EXTENSION") (pin "17") (pinfunction "17_17") (pintype "passive"))
      (node (ref "IC4") (pin "22") (pinfunction "(SCL)PC0_22") (pintype "bidirectional"))
    )
    (net (code "18") (name "EXTENSION-18") (class "Default")
      (node (ref "EEPROM") (pin "1") (pinfunction "1_1") (pintype "passive"))
      (node (ref "EXTENSION") (pin "18") (pinfunction "18_18") (pintype "passive"))
      (node (ref "IC4") (pin "23") (pinfunction "(SDA)PC1_23") (pintype "bidirectional"))
    )
    (net (code "19") (name "EXTENSION-19") (class "Default")
      (node (ref "EXTENSION") (pin "19") (pinfunction "19_19") (pintype "passive"))
      (node (ref "IC4") (pin "24") (pinfunction "(TCK)PC2_24") (pintype "bidirectional"))
      (node (ref "JTAG") (pin "1") (pinfunction "1_1") (pintype "passive"))
    )
    (net (code "20") (name "EXTENSION-21") (class "Default")
      (node (ref "EXTENSION") (pin "21") (pinfunction "21_21") (pintype "passive"))
      (node (ref "IC4") (pin "25") (pinfunction "(TMS)PC3_25") (pintype "bidirectional"))
      (node (ref "JTAG") (pin "5") (pinfunction "5_5") (pintype "passive"))
    )
    (net (code "21") (name "EXTENSION-22") (class "Default")
      (node (ref "EXTENSION") (pin "22") (pinfunction "22_22") (pintype "passive"))
      (node (ref "IC4") (pin "26") (pinfunction "(TDO)PC4_26") (pintype "bidirectional"))
      (node (ref "JTAG") (pin "3") (pinfunction "3_3") (pintype "passive"))
    )
    (net (code "22") (name "EXTENSION-23") (class "Default")
      (node (ref "EXTENSION") (pin "23") (pinfunction "23_23") (pintype "passive"))
      (node (ref "IC4") (pin "27") (pinfunction "(TDI)PC5_27") (pintype "bidirectional"))
      (node (ref "JTAG") (pin "9") (pinfunction "9_9") (pintype "passive"))
    )
    (net (code "23") (name "EXTENSION-24") (class "Default")
      (node (ref "EXTENSION") (pin "24") (pinfunction "24_24") (pintype "passive"))
      (node (ref "IC4") (pin "28") (pinfunction "(TOSC1)PC6_28") (pintype "bidirectional"))
    )
    (net (code "24") (name "EXTENSION-25") (class "Default")
      (node (ref "EXTENSION") (pin "25") (pinfunction "25_25") (pintype "passive"))
      (node (ref "IC4") (pin "29") (pinfunction "(TOSC2)PC7_29") (pintype "bidirectional"))
    )
    (net (code "25") (name "EXTENSION-28") (class "Default")
      (node (ref "EXTENSION") (pin "28") (pinfunction "28_28") (pintype "passive"))
      (node (ref "IC2") (pin "6") (pinfunction "(INT0)PD2_6") (pintype "bidirectional"))
      (node (ref "IC3") (pin "4") (pinfunction "PD2(INT0)_4") (pintype "bidirectional"))
      (node (ref "IC4") (pin "16") (pinfunction "(INT0)PD2_16") (pintype "bidirectional"))
      (node (ref "S1") (pin "3") (pinfunction "P_3") (pintype "passive"))
      (node (ref "S1") (pin "4") (pinfunction "P1_4") (pintype "passive"))
    )
    (net (code "26") (name "EXTENSION-29") (class "Default")
      (node (ref "EXTENSION") (pin "29") (pinfunction "29_29") (pintype "passive"))
      (node (ref "IC2") (pin "7") (pinfunction "(INT1)PD3_7") (pintype "bidirectional"))
      (node (ref "IC3") (pin "5") (pinfunction "PD3(INT1)_5") (pintype "bidirectional"))
      (node (ref "IC4") (pin "17") (pinfunction "(INT1)PD3_17") (pintype "bidirectional"))
      (node (ref "S2") (pin "3") (pinfunction "P_3") (pintype "passive"))
      (node (ref "S2") (pin "4") (pinfunction "P1_4") (pintype "passive"))
    )
    (net (code "27") (name "EXTENSION-30") (class "Default")
      (node (ref "EXTENSION") (pin "30") (pinfunction "30_30") (pintype "passive"))
      (node (ref "IC2") (pin "8") (pinfunction "(T0)PD4_8") (pintype "bidirectional"))
      (node (ref "IC3") (pin "6") (pinfunction "PD4(XCK/T0)_6") (pintype "bidirectional"))
      (node (ref "IC4") (pin "18") (pinfunction "(OC1B)PD4_18") (pintype "bidirectional"))
      (node (ref "S3") (pin "3") (pinfunction "P_3") (pintype "passive"))
      (node (ref "S3") (pin "4") (pinfunction "P1_4") (pintype "passive"))
    )
    (net (code "28") (name "EXTENSION-31") (class "Default")
      (node (ref "EXTENSION") (pin "31") (pinfunction "31_31") (pintype "passive"))
      (node (ref "IC2") (pin "9") (pinfunction "(T1)PD5_9") (pintype "bidirectional"))
      (node (ref "IC3") (pin "11") (pinfunction "PD5(T1)_11") (pintype "bidirectional"))
      (node (ref "IC4") (pin "19") (pinfunction "(OC1A)PD5_19") (pintype "bidirectional"))
      (node (ref "R4") (pin "2") (pinfunction "2_2") (pintype "passive"))
    )
    (net (code "29") (name "EXTENSION-32") (class "Default")
      (node (ref "EXTENSION") (pin "32") (pinfunction "32_32") (pintype "passive"))
      (node (ref "IC2") (pin "11") (pinfunction "(ICP)PD6_11") (pintype "bidirectional"))
      (node (ref "IC3") (pin "12") (pinfunction "PD6(AIN0)_12") (pintype "bidirectional"))
      (node (ref "IC4") (pin "20") (pinfunction "(ICP)PD6_20") (pintype "bidirectional"))
      (node (ref "R3") (pin "2") (pinfunction "2_2") (pintype "passive"))
    )
    (net (code "30") (name "EXTENSION-33") (class "Default")
      (node (ref "EXTENSION") (pin "33") (pinfunction "33_33") (pintype "passive"))
      (node (ref "IC3") (pin "13") (pinfunction "PD7(AIN1)_13") (pintype "bidirectional"))
      (node (ref "IC4") (pin "21") (pinfunction "(OC2)PD7_21") (pintype "bidirectional"))
      (node (ref "SJ4") (pin "2") (pinfunction "2_2") (pintype "passive"))
    )
    (net (code "31") (name "GND") (class "Default")
      (node (ref "A0") (pin "3") (pinfunction "3_3") (pintype "passive"))
      (node (ref "A1") (pin "3") (pinfunction "3_3") (pintype "passive"))
      (node (ref "A2") (pin "3") (pinfunction "3_3") (pintype "passive"))
      (node (ref "C1") (pin "2") (pinfunction "2_2") (pintype "passive"))
      (node (ref "C10") (pin "2") (pinfunction "2_2") (pintype "passive"))
      (node (ref "C11") (pin "2") (pinfunction "2_2") (pintype "passive"))
      (node (ref "C12") (pin "2") (pinfunction "2_2") (pintype "passive"))
      (node (ref "C13") (pin "2") (pinfunction "2_2") (pintype "passive"))
      (node (ref "C14") (pin "-") (pinfunction "-_-") (pintype "passive"))
      (node (ref "C15") (pin "-") (pinfunction "-_-") (pintype "passive"))
      (node (ref "C16") (pin "2") (pinfunction "2_2") (pintype "passive"))
      (node (ref "C17") (pin "2") (pinfunction "2_2") (pintype "passive"))
      (node (ref "C18") (pin "2") (pinfunction "2_2") (pintype "passive"))
      (node (ref "C2") (pin "2") (pinfunction "2_2") (pintype "passive"))
      (node (ref "C3") (pin "2") (pinfunction "2_2") (pintype "passive"))
      (node (ref "C4") (pin "2") (pinfunction "2_2") (pintype "passive"))
      (node (ref "C5") (pin "2") (pinfunction "2_2") (pintype "passive"))
      (node (ref "C6") (pin "2") (pinfunction "2_2") (pintype "passive"))
      (node (ref "C7") (pin "2") (pinfunction "2_2") (pintype "passive"))
      (node (ref "C8") (pin "2") (pinfunction "2_2") (pintype "passive"))
      (node (ref "C9") (pin "2") (pinfunction "2_2") (pintype "passive"))
      (node (ref "EXTENSION") (pin "35") (pinfunction "35_35") (pintype "passive"))
      (node (ref "EXTENSION") (pin "37") (pinfunction "37_37") (pintype "passive"))
      (node (ref "EXTENSION") (pin "39") (pinfunction "39_39") (pintype "passive"))
      (node (ref "H1") (pin "B3,2") (pinfunction "MOUNT_B3,2") (pintype "passive"))
      (node (ref "H3") (pin "B3,2") (pinfunction "MOUNT_B3,2") (pintype "passive"))
      (node (ref "H4") (pin "B3,2") (pinfunction "MOUNT_B3,2") (pintype "passive"))
      (node (ref "H5") (pin "B3,2") (pinfunction "MOUNT_B3,2") (pintype "passive"))
      (node (ref "HWB") (pin "1") (pinfunction "P_1") (pintype "passive"))
      (node (ref "IC1") (pin "4") (pinfunction "GND_4") (pintype "power_in"))
      (node (ref "IC2") (pin "10") (pinfunction "GND_10") (pintype "power_in"))
      (node (ref "IC3") (pin "22") (pinfunction "GND_22") (pintype "power_in"))
      (node (ref "IC3") (pin "8") (pinfunction "GND_8") (pintype "power_in"))
      (node (ref "IC4") (pin "11") (pinfunction "GND_11") (pintype "power_in"))
      (node (ref "IC4") (pin "31") (pinfunction "GND_31") (pintype "power_in"))
      (node (ref "IC5") (pin "28") (pinfunction "UGND_28") (pintype "power_in"))
      (node (ref "IC5") (pin "3") (pinfunction "GND_3") (pintype "power_in"))
      (node (ref "IC6") (pin "4") (pinfunction "GND_4") (pintype "power_in"))
      (node (ref "IC7") (pin "1") (pinfunction "GND_1") (pintype "bidirectional"))
      (node (ref "ISP") (pin "2") (pinfunction "2_2") (pintype "passive"))
      (node (ref "ISP-10") (pin "10") (pinfunction "10_10") (pintype "passive"))
      (node (ref "ISP-10") (pin "4") (pinfunction "4_4") (pintype "passive"))
      (node (ref "ISP-10") (pin "6") (pinfunction "6_6") (pintype "passive"))
      (node (ref "ISP-10") (pin "8") (pinfunction "8_8") (pintype "passive"))
      (node (ref "ISP-6") (pin "6") (pinfunction "6_6") (pintype "passive"))
      (node (ref "ISP-6/2") (pin "6") (pinfunction "6_6") (pintype "passive"))
      (node (ref "JTAG") (pin "10") (pinfunction "10_10") (pintype "passive"))
      (node (ref "JTAG") (pin "2") (pinfunction "2_2") (pintype "passive"))
      (node (ref "LED1") (pin "K") (pinfunction "C_K") (pintype "passive"))
      (node (ref "LED2") (pin "K") (pinfunction "C_K") (pintype "passive"))
      (node (ref "M32U-PORTC/SUPP") (pin "1") (pinfunction "1_1") (pintype "bidirectional"))
      (node (ref "PDI") (pin "6") (pinfunction "6_6") (pintype "passive"))
      (node (ref "POTI1") (pin "A") (pinfunction "A_A") (pintype "passive"))
      (node (ref "POTI2") (pin "A") (pinfunction "A_A") (pintype "passive"))
      (node (ref "POWER") (pin "C") (pinfunction "C_C") (pintype "passive"))
      (node (ref "PROG") (pin "C") (pinfunction "C_C") (pintype "passive"))
      (node (ref "Q4") (pin "2") (pinfunction "GND_2") (pintype "bidirectional"))
      (node (ref "RESET") (pin "1") (pinfunction "S_1") (pintype "passive"))
      (node (ref "RESET") (pin "2") (pinfunction "S1_2") (pintype "passive"))
      (node (ref "RST") (pin "1") (pinfunction "P_1") (pintype "passive"))
      (node (ref "S1") (pin "1") (pinfunction "S_1") (pintype "passive"))
      (node (ref "S1") (pin "2") (pinfunction "S1_2") (pintype "passive"))
      (node (ref "S2") (pin "1") (pinfunction "S_1") (pintype "passive"))
      (node (ref "S2") (pin "2") (pinfunction "S1_2") (pintype "passive"))
      (node (ref "S3") (pin "1") (pinfunction "S_1") (pintype "passive"))
      (node (ref "S3") (pin "2") (pinfunction "S1_2") (pintype "passive"))
      (node (ref "SPI") (pin "9") (pinfunction "9_9") (pintype "passive"))
      (node (ref "SPKR1") (pin "-") (pinfunction "-_-") (pintype "bidirectional"))
      (node (ref "TPI") (pin "6") (pinfunction "6_6") (pintype "passive"))
      (node (ref "USART") (pin "1") (pinfunction "1_1") (pintype "bidirectional"))
      (node (ref "USB") (pin "4") (pinfunction "4_4") (pintype "passive"))
      (node (ref "WP") (pin "3") (pinfunction "3_3") (pintype "passive"))
      (node (ref "X1") (pin "GND") (pinfunction "GND_GND") (pintype "passive"))
      (node (ref "X1") (pin "S1") (pinfunction "S1_S1") (pintype "passive"))
      (node (ref "X1") (pin "S2") (pinfunction "S2_S2") (pintype "passive"))
    )
    (net (code "32") (name "MISO") (class "Default")
      (node (ref "EXTENSION") (pin "15") (pinfunction "15_15") (pintype "passive"))
      (node (ref "IC1") (pin "6") (pinfunction "PB1/PCINT1/AIN1/OC0B/INT0/MISO_6") (pintype "bidirectional"))
      (node (ref "IC2") (pin "18") (pinfunction "(MISO)PB6_18") (pintype "bidirectional"))
      (node (ref "IC3") (pin "18") (pinfunction "PB4(MISO)_18") (pintype "bidirectional"))
      (node (ref "IC4") (pin "7") (pinfunction "(MISO)PB6_7") (pintype "bidirectional"))
      (node (ref "IC5") (pin "17") (pinfunction "(PDO/MISO/PCINT3)PB3_17") (pintype "bidirectional"))
      (node (ref "ISP-10") (pin "9") (pinfunction "9_9") (pintype "passive"))
      (node (ref "ISP-6") (pin "1") (pinfunction "1_1") (pintype "passive"))
      (node (ref "ISP-6/2") (pin "1") (pinfunction "1_1") (pintype "passive"))
      (node (ref "M32U-PORTB") (pin "4") (pinfunction "4_4") (pintype "bidirectional"))
      (node (ref "SPI") (pin "6") (pinfunction "6_6") (pintype "passive"))
    )
    (net (code "33") (name "MOSI") (class "Default")
      (node (ref "EXTENSION") (pin "14") (pinfunction "14_14") (pintype "passive"))
      (node (ref "IC1") (pin "5") (pinfunction "PB0/PCINT0/AIN0/OC0A/MOSI_5") (pintype "bidirectional"))
      (node (ref "IC2") (pin "17") (pinfunction "(MOSI)PB5_17") (pintype "bidirectional"))
      (node (ref "IC3") (pin "17") (pinfunction "PB3(MOSI/OC2)_17") (pintype "bidirectional"))
      (node (ref "IC4") (pin "6") (pinfunction "(MOSI)PB5_6") (pintype "bidirectional"))
      (node (ref "IC5") (pin "16") (pinfunction "(PDI/MOSI/PCINT2)PB2_16") (pintype "bidirectional"))
      (node (ref "ISP-10") (pin "1") (pinfunction "1_1") (pintype "passive"))
      (node (ref "ISP-6") (pin "4") (pinfunction "4_4") (pintype "passive"))
      (node (ref "ISP-6/2") (pin "4") (pinfunction "4_4") (pintype "passive"))
      (node (ref "M32U-PORTB") (pin "3") (pinfunction "3_3") (pintype "bidirectional"))
      (node (ref "SPI") (pin "7") (pinfunction "7_7") (pintype "passive"))
    )
    (net (code "34") (name "Net-(ADC-Pad2)") (class "Default")
      (node (ref "ADC") (pin "2") (pinfunction "2_2") (pintype "passive"))
      (node (ref "POTI2") (pin "S") (pinfunction "S_S") (pintype "passive"))
    )
    (net (code "35") (name "Net-(ADC-Pad4)") (class "Default")
      (node (ref "ADC") (pin "4") (pinfunction "4_4") (pintype "passive"))
      (node (ref "POTI1") (pin "S") (pinfunction "S_S") (pintype "passive"))
    )
    (net (code "36") (name "Net-(F1-Pad1)") (class "Default")
      (node (ref "F1") (pin "1") (pinfunction "1_1") (pintype "passive"))
      (node (ref "X1") (pin "VCC") (pinfunction "VCC_VCC") (pintype "passive"))
    )
    (net (code "37") (name "Net-(F1-Pad2)") (class "Default")
      (node (ref "F1") (pin "2") (pinfunction "2_2") (pintype "passive"))
      (node (ref "L1") (pin "1") (pinfunction "1_1") (pintype "passive"))
    )
    (net (code "38") (name "Net-(IC2-XTAL1)") (class "Default")
      (node (ref "C6") (pin "1") (pinfunction "1_1") (pintype "passive"))
      (node (ref "IC2") (pin "5") (pinfunction "XTAL1_5") (pintype "bidirectional"))
      (node (ref "Q1") (pin "1") (pinfunction "1_1") (pintype "passive"))
    )
    (net (code "39") (name "Net-(IC2-XTAL2)") (class "Default")
      (node (ref "C3") (pin "1") (pinfunction "1_1") (pintype "passive"))
      (node (ref "IC2") (pin "4") (pinfunction "XTAL2_4") (pintype "bidirectional"))
      (node (ref "Q1") (pin "2") (pinfunction "2_2") (pintype "passive"))
    )
    (net (code "40") (name "Net-(IC3-PB6(XTAL1{slash}TOSC1))") (class "Default")
      (node (ref "C8") (pin "1") (pinfunction "1_1") (pintype "passive"))
      (node (ref "IC3") (pin "9") (pinfunction "PB6(XTAL1/TOSC1)_9") (pintype "bidirectional"))
      (node (ref "Q2") (pin "2") (pinfunction "2_2") (pintype "passive"))
    )
    (net (code "41") (name "Net-(IC3-PB7(XTAL2{slash}TOSC2))") (class "Default")
      (node (ref "C11") (pin "1") (pinfunction "1_1") (pintype "passive"))
      (node (ref "IC3") (pin "10") (pinfunction "PB7(XTAL2/TOSC2)_10") (pintype "bidirectional"))
      (node (ref "Q2") (pin "1") (pinfunction "1_1") (pintype "passive"))
    )
    (net (code "42") (name "Net-(IC4-XTAL1)") (class "Default")
      (node (ref "C13") (pin "1") (pinfunction "1_1") (pintype "passive"))
      (node (ref "IC4") (pin "13") (pinfunction "XTAL1_13") (pintype "bidirectional"))
      (node (ref "Q3") (pin "1") (pinfunction "1_1") (pintype "passive"))
    )
    (net (code "43") (name "Net-(IC4-XTAL2)") (class "Default")
      (node (ref "C5") (pin "1") (pinfunction "1_1") (pintype "passive"))
      (node (ref "IC4") (pin "12") (pinfunction "XTAL2_12") (pintype "bidirectional"))
      (node (ref "Q3") (pin "2") (pinfunction "2_2") (pintype "passive"))
    )
    (net (code "44") (name "Net-(IC5-(AIN0{slash}INT1)PD1)") (class "Default")
      (node (ref "IC5") (pin "7") (pinfunction "(AIN0/INT1)PD1_7") (pintype "bidirectional"))
      (node (ref "M32U-PORTD") (pin "2") (pinfunction "2_2") (pintype "bidirectional"))
    )
    (net (code "45") (name "Net-(IC5-(INT4{slash}ICP1{slash}CLKO)PC7)") (class "Default")
      (node (ref "IC5") (pin "22") (pinfunction "(INT4/ICP1/CLKO)PC7_22") (pintype "bidirectional"))
      (node (ref "M32U-PORTC/SUPP") (pin "8") (pinfunction "8_8") (pintype "bidirectional"))
    )
    (net (code "46") (name "Net-(IC5-(INT5{slash}AIN3)PD4)") (class "Default")
      (node (ref "IC5") (pin "10") (pinfunction "(INT5/AIN3)PD4_10") (pintype "bidirectional"))
      (node (ref "M32U-PORTD") (pin "5") (pinfunction "5_5") (pintype "bidirectional"))
    )
    (net (code "47") (name "Net-(IC5-(OC.0B{slash}INT0)PD0)") (class "Default")
      (node (ref "IC5") (pin "6") (pinfunction "(OC.0B/INT0)PD0_6") (pintype "bidirectional"))
      (node (ref "ISP") (pin "1") (pinfunction "1_1") (pintype "passive"))
      (node (ref "M32U-PORTD") (pin "1") (pinfunction "1_1") (pintype "bidirectional"))
    )
    (net (code "48") (name "Net-(IC5-(OC.1A{slash}PCINT8)PC6)") (class "Default")
      (node (ref "IC5") (pin "23") (pinfunction "(OC.1A/PCINT8)PC6_23") (pintype "bidirectional"))
      (node (ref "M32U-PORTC/SUPP") (pin "7") (pinfunction "7_7") (pintype "bidirectional"))
    )
    (net (code "49") (name "Net-(IC5-(PCINT5)PB5)") (class "Default")
      (node (ref "IC5") (pin "19") (pinfunction "(PCINT5)PB5_19") (pintype "bidirectional"))
      (node (ref "M32U-PORTB") (pin "6") (pinfunction "6_6") (pintype "bidirectional"))
    )
    (net (code "50") (name "Net-(IC5-(PCINT6)PB6)") (class "Default")
      (node (ref "IC5") (pin "20") (pinfunction "(PCINT6)PB6_20") (pintype "bidirectional"))
      (node (ref "M32U-PORTB") (pin "7") (pinfunction "7_7") (pintype "bidirectional"))
      (node (ref "R6") (pin "2") (pinfunction "2_2") (pintype "passive"))
    )
    (net (code "51") (name "Net-(IC5-(PCINT7{slash}OC.0A{slash}OC.1C)PB7)") (class "Default")
      (node (ref "IC5") (pin "21") (pinfunction "(PCINT7/OC.0A/OC.1C)PB7_21") (pintype "bidirectional"))
      (node (ref "M32U-PORTB") (pin "8") (pinfunction "8_8") (pintype "bidirectional"))
    )
    (net (code "52") (name "Net-(IC5-(PCINT9{slash}OC.1B)PC5)") (class "Default")
      (node (ref "IC5") (pin "25") (pinfunction "(PCINT9/OC.1B)PC5_25") (pintype "bidirectional"))
      (node (ref "M32U-PORTC/SUPP") (pin "6") (pinfunction "6_6") (pintype "bidirectional"))
    )
    (net (code "53") (name "Net-(IC5-(PCINT10)PC4)") (class "Default")
      (node (ref "IC5") (pin "26") (pinfunction "(PCINT10)PC4_26") (pintype "bidirectional"))
      (node (ref "M32U-PORTC/SUPP") (pin "5") (pinfunction "5_5") (pintype "bidirectional"))
    )
    (net (code "54") (name "Net-(IC5-(PCINT11{slash}AIN2)PC2)") (class "Default")
      (node (ref "IC5") (pin "5") (pinfunction "(PCINT11/AIN2)PC2_5") (pintype "bidirectional"))
      (node (ref "M32U-PORTC/SUPP") (pin "4") (pinfunction "4_4") (pintype "bidirectional"))
    )
    (net (code "55") (name "Net-(IC5-(~{SS{slash}PCINT0})PB0)") (class "Default")
      (node (ref "IC5") (pin "14") (pinfunction "(~{SS/PCINT0})PB0_14") (pintype "bidirectional"))
      (node (ref "M32U-PORTB") (pin "1") (pinfunction "1_1") (pintype "bidirectional"))
    )
    (net (code "56") (name "Net-(IC5-D+)") (class "Default")
      (node (ref "IC5") (pin "29") (pinfunction "D+_29") (pintype "power_in"))
      (node (ref "R9") (pin "2") (pinfunction "2_2") (pintype "passive"))
    )
    (net (code "57") (name "Net-(IC5-D-)") (class "Default")
      (node (ref "IC5") (pin "30") (pinfunction "D-_30") (pintype "power_in"))
      (node (ref "R10") (pin "2") (pinfunction "2_2") (pintype "passive"))
    )
    (net (code "58") (name "Net-(IC5-UCAP)") (class "Default")
      (node (ref "C9") (pin "1") (pinfunction "1_1") (pintype "passive"))
      (node (ref "IC5") (pin "27") (pinfunction "UCAP_27") (pintype "power_in"))
    )
    (net (code "59") (name "Net-(IC5-XTAL1)") (class "Default")
      (node (ref "IC5") (pin "1") (pinfunction "XTAL1_1") (pintype "bidirectional"))
      (node (ref "Q4") (pin "1") (pinfunction "Q1_1") (pintype "bidirectional"))
    )
    (net (code "60") (name "Net-(IC5-XTAL2(PC0))") (class "Default")
      (node (ref "IC5") (pin "2") (pinfunction "XTAL2(PC0)_2") (pintype "bidirectional"))
      (node (ref "Q4") (pin "3") (pinfunction "Q2_3") (pintype "bidirectional"))
    )
    (net (code "61") (name "Net-(IC6-A0)") (class "Default")
      (node (ref "A0") (pin "2") (pinfunction "2_2") (pintype "passive"))
      (node (ref "IC6") (pin "1") (pinfunction "A0_1") (pintype "input"))
    )
    (net (code "62") (name "Net-(IC6-A1)") (class "Default")
      (node (ref "A1") (pin "2") (pinfunction "2_2") (pintype "passive"))
      (node (ref "IC6") (pin "2") (pinfunction "A1_2") (pintype "input"))
    )
    (net (code "63") (name "Net-(IC6-A2)") (class "Default")
      (node (ref "A2") (pin "2") (pinfunction "2_2") (pintype "passive"))
      (node (ref "IC6") (pin "3") (pinfunction "A2_3") (pintype "input"))
    )
    (net (code "64") (name "Net-(IC6-SCL)") (class "Default")
      (node (ref "EEPROM") (pin "4") (pinfunction "4_4") (pintype "passive"))
      (node (ref "EEPROM") (pin "8") (pinfunction "8_8") (pintype "passive"))
      (node (ref "IC6") (pin "6") (pinfunction "SCL_6") (pintype "bidirectional"))
      (node (ref "R11") (pin "1") (pinfunction "1_1") (pintype "passive"))
    )
    (net (code "65") (name "Net-(IC6-SDA)") (class "Default")
      (node (ref "EEPROM") (pin "2") (pinfunction "2_2") (pintype "passive"))
      (node (ref "EEPROM") (pin "6") (pinfunction "6_6") (pintype "passive"))
      (node (ref "IC6") (pin "5") (pinfunction "SDA_5") (pintype "bidirectional"))
      (node (ref "R12") (pin "1") (pinfunction "1_1") (pintype "passive"))
    )
    (net (code "66") (name "Net-(IC6-WP)") (class "Default")
      (node (ref "IC6") (pin "7") (pinfunction "WP_7") (pintype "input"))
      (node (ref "WP") (pin "2") (pinfunction "2_2") (pintype "passive"))
    )
    (net (code "67") (name "Net-(IC7-IN)") (class "Default")
      (node (ref "C18") (pin "1") (pinfunction "1_1") (pintype "passive"))
      (node (ref "IC7") (pin "3") (pinfunction "IN_3") (pintype "bidirectional"))
      (node (ref "PWR") (pin "1") (pinfunction "1_1") (pintype "passive"))
    )
    (net (code "68") (name "Net-(L1-Pad2)") (class "Default")
      (node (ref "L1") (pin "2") (pinfunction "2_2") (pintype "passive"))
      (node (ref "PWR") (pin "2") (pinfunction "2_2") (pintype "passive"))
    )
    (net (code "69") (name "Net-(LED1-PadA)") (class "Default")
      (node (ref "LED1") (pin "A") (pinfunction "A_A") (pintype "passive"))
      (node (ref "SJ2") (pin "1") (pinfunction "1_1") (pintype "passive"))
    )
    (net (code "70") (name "Net-(LED2-PadA)") (class "Default")
      (node (ref "LED2") (pin "A") (pinfunction "A_A") (pintype "passive"))
      (node (ref "SJ3") (pin "1") (pinfunction "1_1") (pintype "passive"))
    )
    (net (code "71") (name "Net-(POWER-PadA)") (class "Default")
      (node (ref "POWER") (pin "A") (pinfunction "A_A") (pintype "passive"))
      (node (ref "R7") (pin "1") (pinfunction "1_1") (pintype "passive"))
    )
    (net (code "72") (name "Net-(PROG-PadA)") (class "Default")
      (node (ref "PROG") (pin "A") (pinfunction "A_A") (pintype "passive"))
      (node (ref "R6") (pin "1") (pinfunction "1_1") (pintype "passive"))
    )
    (net (code "73") (name "Net-(R3-Pad1)") (class "Default")
      (node (ref "R3") (pin "1") (pinfunction "1_1") (pintype "passive"))
      (node (ref "SJ2") (pin "2") (pinfunction "2_2") (pintype "passive"))
    )
    (net (code "74") (name "Net-(R4-Pad1)") (class "Default")
      (node (ref "R4") (pin "1") (pinfunction "1_1") (pintype "passive"))
      (node (ref "SJ3") (pin "2") (pinfunction "2_2") (pintype "passive"))
    )
    (net (code "75") (name "Net-(R9-Pad1)") (class "Default")
      (node (ref "R9") (pin "1") (pinfunction "1_1") (pintype "passive"))
      (node (ref "USB") (pin "3") (pinfunction "3_3") (pintype "passive"))
      (node (ref "X1") (pin "D+") (pinfunction "D+_D+") (pintype "passive"))
    )
    (net (code "76") (name "Net-(R10-Pad1)") (class "Default")
      (node (ref "R10") (pin "1") (pinfunction "1_1") (pintype "passive"))
      (node (ref "USB") (pin "2") (pinfunction "2_2") (pintype "passive"))
      (node (ref "X1") (pin "D-") (pinfunction "D-_D-") (pintype "passive"))
    )
    (net (code "77") (name "Net-(SJ4-Pad1)") (class "Default")
      (node (ref "SJ4") (pin "1") (pinfunction "1_1") (pintype "passive"))
      (node (ref "SPKR1") (pin "+") (pinfunction "+_+") (pintype "bidirectional"))
    )
    (net (code "78") (name "PD0") (class "Default")
      (node (ref "1") (pin "1") (pinfunction "3_1") (pintype "passive"))
      (node (ref "2") (pin "2") (pinfunction "1_2") (pintype "passive"))
      (node (ref "EXTENSION") (pin "26") (pinfunction "26_26") (pintype "passive"))
      (node (ref "IC2") (pin "2") (pinfunction "(RXD)PD0_2") (pintype "bidirectional"))
      (node (ref "IC3") (pin "2") (pinfunction "PD0(RXD)_2") (pintype "bidirectional"))
      (node (ref "IC4") (pin "14") (pinfunction "(RXD)PD0_14") (pintype "bidirectional"))
      (node (ref "SERIAL") (pin "3") (pinfunction "3_3") (pintype "passive"))
    )
    (net (code "79") (name "PD1") (class "Default")
      (node (ref "1") (pin "2") (pinfunction "1_2") (pintype "passive"))
      (node (ref "2") (pin "1") (pinfunction "3_1") (pintype "passive"))
      (node (ref "EXTENSION") (pin "27") (pinfunction "27_27") (pintype "passive"))
      (node (ref "IC2") (pin "3") (pinfunction "(TXD)PD1_3") (pintype "bidirectional"))
      (node (ref "IC3") (pin "3") (pinfunction "PD1(TXD)_3") (pintype "bidirectional"))
      (node (ref "IC4") (pin "15") (pinfunction "(TXD)PD1_15") (pintype "bidirectional"))
      (node (ref "SERIAL") (pin "1") (pinfunction "1_1") (pintype "passive"))
    )
    (net (code "80") (name "PROG-RESET") (class "Default")
      (node (ref "IC5") (pin "24") (pinfunction "(PC1/DW)~{RESET}_24") (pintype "bidirectional"))
      (node (ref "M32U-PORTC/SUPP") (pin "3") (pinfunction "3_3") (pintype "bidirectional"))
      (node (ref "P-RST") (pin "1") (pinfunction "1_1") (pintype "passive"))
      (node (ref "R8") (pin "1") (pinfunction "1_1") (pintype "passive"))
      (node (ref "RST") (pin "2") (pinfunction "S_2") (pintype "passive"))
    )
    (net (code "81") (name "PROG-RXD") (class "Default")
      (node (ref "IC5") (pin "8") (pinfunction "(RXD1/AIN1/INT2)PD2_8") (pintype "bidirectional"))
      (node (ref "M32U-PORTD") (pin "3") (pinfunction "3_3") (pintype "bidirectional"))
      (node (ref "R13") (pin "1") (pinfunction "1_1") (pintype "passive"))
      (node (ref "SERIAL") (pin "2") (pinfunction "2_2") (pintype "passive"))
    )
    (net (code "82") (name "PROG-TXD") (class "Default")
      (node (ref "IC5") (pin "9") (pinfunction "(TXD1/INT3)PD3_9") (pintype "bidirectional"))
      (node (ref "M32U-PORTD") (pin "4") (pinfunction "4_4") (pintype "bidirectional"))
      (node (ref "R14") (pin "1") (pinfunction "1_1") (pintype "passive"))
      (node (ref "SERIAL") (pin "4") (pinfunction "4_4") (pintype "passive"))
    )
    (net (code "83") (name "RXD") (class "Default")
      (node (ref "1") (pin "M") (pinfunction "2_M") (pintype "passive"))
      (node (ref "USART") (pin "5") (pinfunction "5_5") (pintype "bidirectional"))
    )
    (net (code "84") (name "SCK") (class "Default")
      (node (ref "EXTENSION") (pin "16") (pinfunction "16_16") (pintype "passive"))
      (node (ref "IC1") (pin "7") (pinfunction "PB2/PCINT2/SCK/ADC1/T0_7") (pintype "bidirectional"))
      (node (ref "IC2") (pin "19") (pinfunction "(SCK)PB7_19") (pintype "bidirectional"))
      (node (ref "IC3") (pin "19") (pinfunction "PB5(SCK)_19") (pintype "bidirectional"))
      (node (ref "IC4") (pin "8") (pinfunction "(SCK)PB7_8") (pintype "bidirectional"))
      (node (ref "IC5") (pin "15") (pinfunction "(SCLK/PCINT1)PB1_15") (pintype "bidirectional"))
      (node (ref "ISP-10") (pin "7") (pinfunction "7_7") (pintype "passive"))
      (node (ref "ISP-6") (pin "3") (pinfunction "3_3") (pintype "passive"))
      (node (ref "ISP-6/2") (pin "3") (pinfunction "3_3") (pintype "passive"))
      (node (ref "M32U-PORTB") (pin "2") (pinfunction "2_2") (pintype "bidirectional"))
      (node (ref "SPI") (pin "8") (pinfunction "8_8") (pintype "passive"))
    )
    (net (code "85") (name "SS") (class "Default")
      (node (ref "EXTENSION") (pin "13") (pinfunction "13_13") (pintype "passive"))
      (node (ref "IC1") (pin "2") (pinfunction "PB3/PCINT3/CLKI/ADC3_2") (pintype "bidirectional"))
      (node (ref "IC2") (pin "16") (pinfunction "PB4_16") (pintype "bidirectional"))
      (node (ref "IC3") (pin "16") (pinfunction "PB2(SS/OC1B)_16") (pintype "bidirectional"))
      (node (ref "IC4") (pin "5") (pinfunction "(SS)PB4_5") (pintype "bidirectional"))
      (node (ref "SPI") (pin "5") (pinfunction "5_5") (pintype "passive"))
    )
    (net (code "86") (name "TXD") (class "Default")
      (node (ref "2") (pin "M") (pinfunction "2_M") (pintype "passive"))
      (node (ref "USART") (pin "4") (pinfunction "4_4") (pintype "bidirectional"))
    )
    (net (code "87") (name "unconnected-(EXTENSION-Pad20)") (class "Default")
      (node (ref "EXTENSION") (pin "20") (pinfunction "20_20") (pintype "passive"))
    )
    (net (code "88") (name "unconnected-(H2-MOUNT-PadB3,2)") (class "Default")
      (node (ref "H2") (pin "B3,2") (pinfunction "MOUNT_B3,2") (pintype "passive"))
    )
    (net (code "89") (name "unconnected-(ISP-10-Pad3)") (class "Default")
      (node (ref "ISP-10") (pin "3") (pinfunction "3_3") (pintype "passive"))
    )
    (net (code "90") (name "unconnected-(JTAG-Pad8)") (class "Default")
      (node (ref "JTAG") (pin "8") (pinfunction "8_8") (pintype "passive"))
    )
    (net (code "91") (name "unconnected-(PDI-Pad3)") (class "Default")
      (node (ref "PDI") (pin "3") (pinfunction "3_3") (pintype "passive"))
    )
    (net (code "92") (name "unconnected-(PDI-Pad4)") (class "Default")
      (node (ref "PDI") (pin "4") (pinfunction "4_4") (pintype "passive"))
    )
    (net (code "93") (name "unconnected-(TPI-Pad4)") (class "Default")
      (node (ref "TPI") (pin "4") (pinfunction "4_4") (pintype "passive"))
    )
    (net (code "94") (name "~{CTS}") (class "Default")
      (node (ref "HWB") (pin "2") (pinfunction "S_2") (pintype "passive"))
      (node (ref "IC5") (pin "13") (pinfunction "(~{CTS}/~{HWB}/AIN6/TO/INT7)PD7_13") (pintype "bidirectional"))
      (node (ref "M32U-PORTD") (pin "8") (pinfunction "8_8") (pintype "bidirectional"))
      (node (ref "USART") (pin "2") (pinfunction "2_2") (pintype "bidirectional"))
    )
    (net (code "95") (name "~{RESET}") (class "Default")
      (node (ref "IC1") (pin "1") (pinfunction "PB5/PCINT5/~{RESET}/ADC0/DW_1") (pintype "bidirectional"))
      (node (ref "IC2") (pin "1") (pinfunction "RESET_1") (pintype "bidirectional"))
      (node (ref "IC3") (pin "1") (pinfunction "PC6(/RESET)_1") (pintype "bidirectional"))
      (node (ref "IC4") (pin "9") (pinfunction "RESET_9") (pintype "input"))
      (node (ref "IC5") (pin "18") (pinfunction "(T1/PCINT4)PB4_18") (pintype "bidirectional"))
      (node (ref "ISP-10") (pin "5") (pinfunction "5_5") (pintype "passive"))
      (node (ref "ISP-6") (pin "5") (pinfunction "5_5") (pintype "passive"))
      (node (ref "ISP-6/2") (pin "5") (pinfunction "5_5") (pintype "passive"))
      (node (ref "JTAG") (pin "6") (pinfunction "6_6") (pintype "passive"))
      (node (ref "M32U-PORTB") (pin "5") (pinfunction "5_5") (pintype "bidirectional"))
      (node (ref "P-RST") (pin "2") (pinfunction "2_2") (pintype "passive"))
      (node (ref "R5") (pin "1") (pinfunction "1_1") (pintype "passive"))
      (node (ref "RESET") (pin "3") (pinfunction "P_3") (pintype "passive"))
      (node (ref "RESET") (pin "4") (pinfunction "P1_4") (pintype "passive"))
      (node (ref "TPI") (pin "5") (pinfunction "5_5") (pintype "passive"))
    )
    (net (code "96") (name "~{RTS}") (class "Default")
      (node (ref "IC5") (pin "12") (pinfunction "(~{RTS}/AIN5/INT6)PD6_12") (pintype "bidirectional"))
      (node (ref "M32U-PORTD") (pin "7") (pinfunction "7_7") (pintype "bidirectional"))
      (node (ref "USART") (pin "6") (pinfunction "6_6") (pintype "bidirectional"))
    )
  )
)
